# vr61-revB.net
KiCad netlist of a schematic drawn in EAGLE
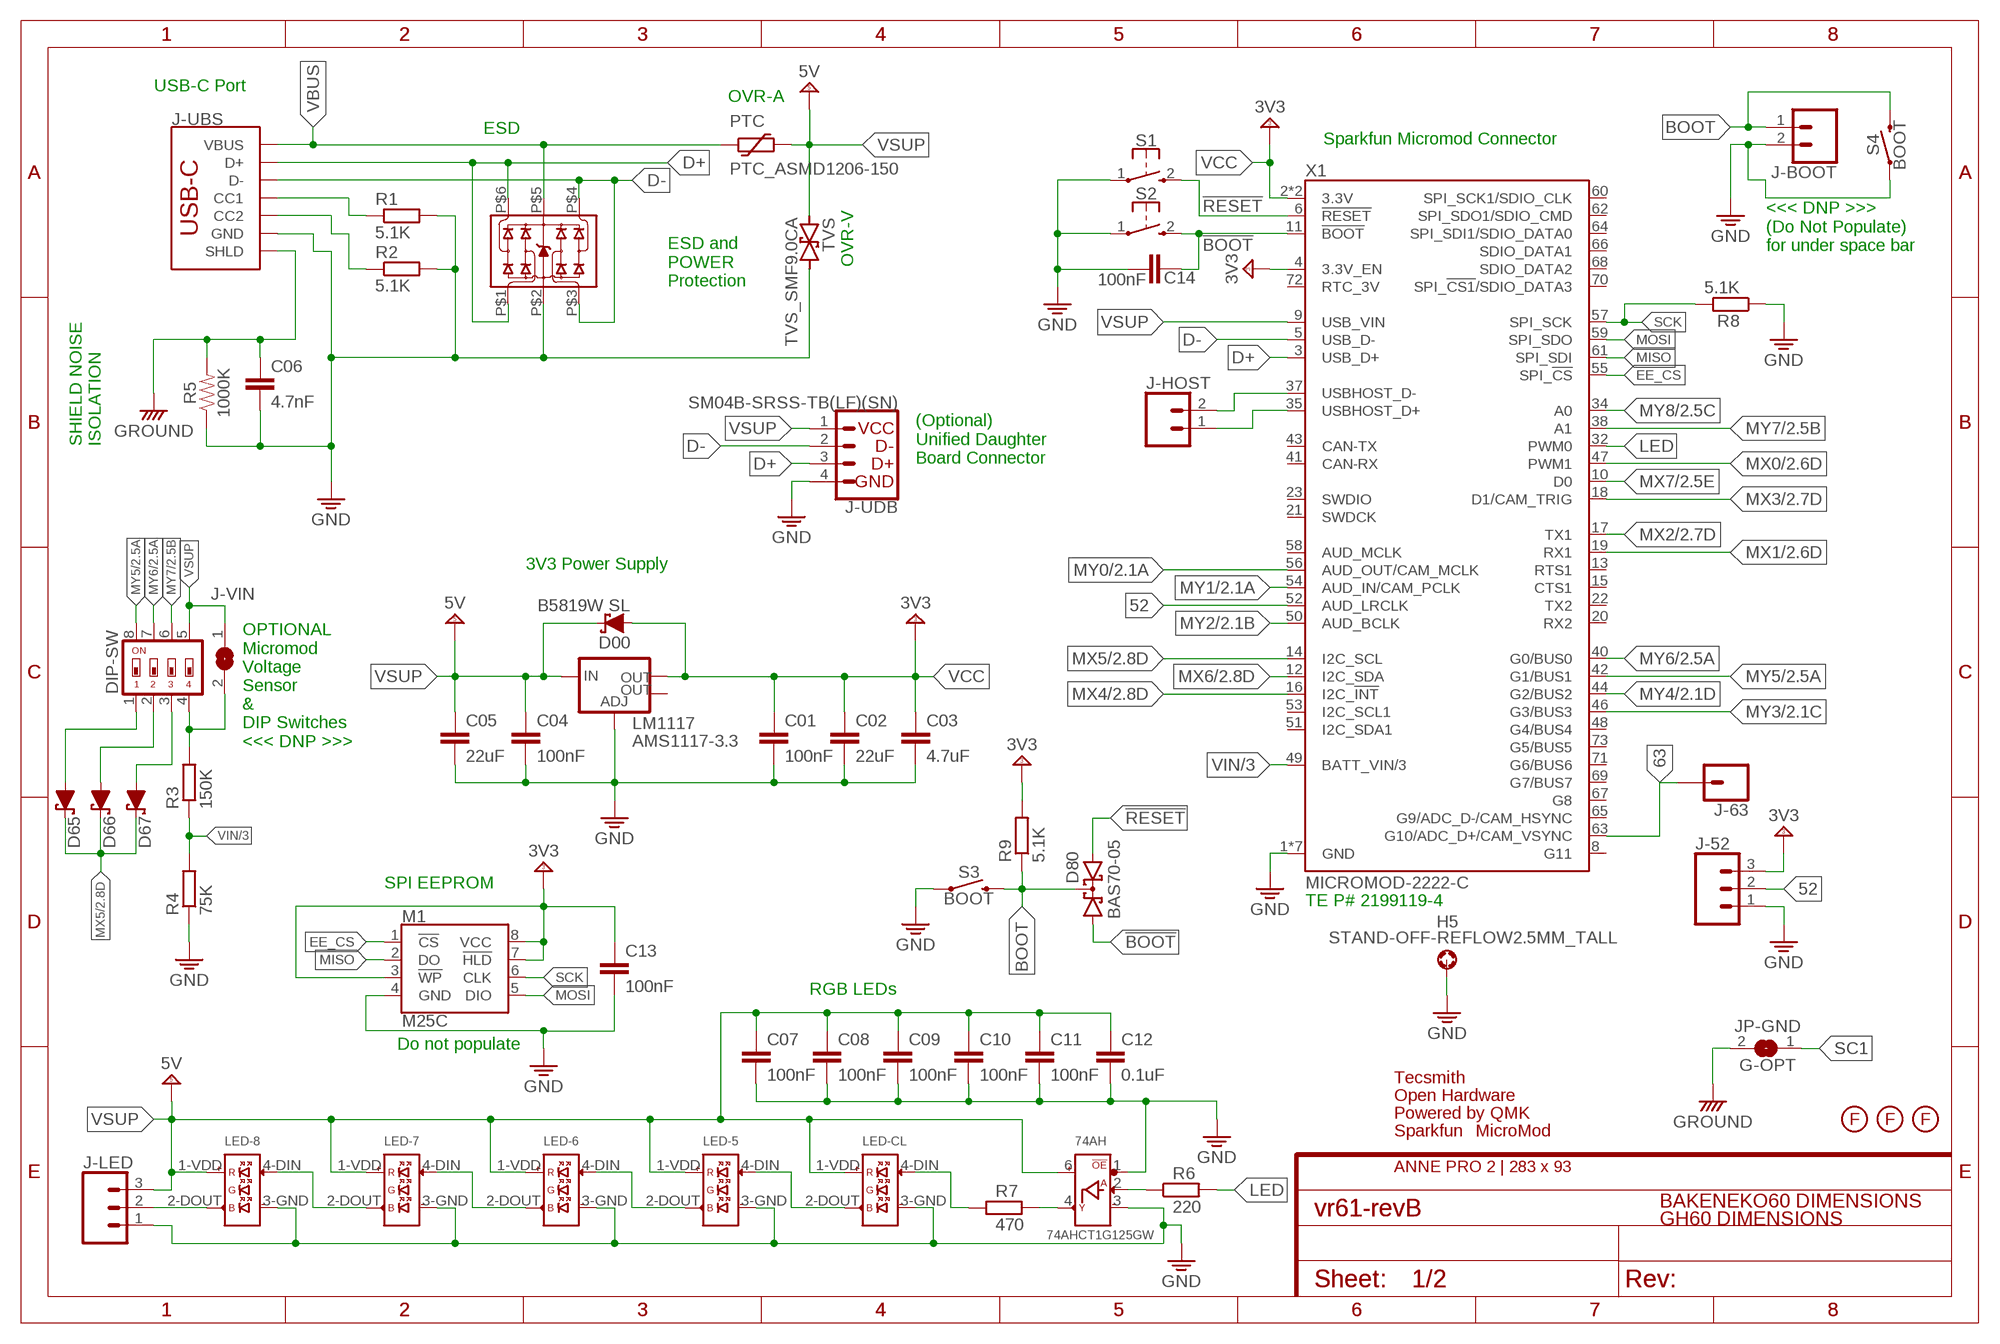
[diagram p0: schematic, sheet 1]
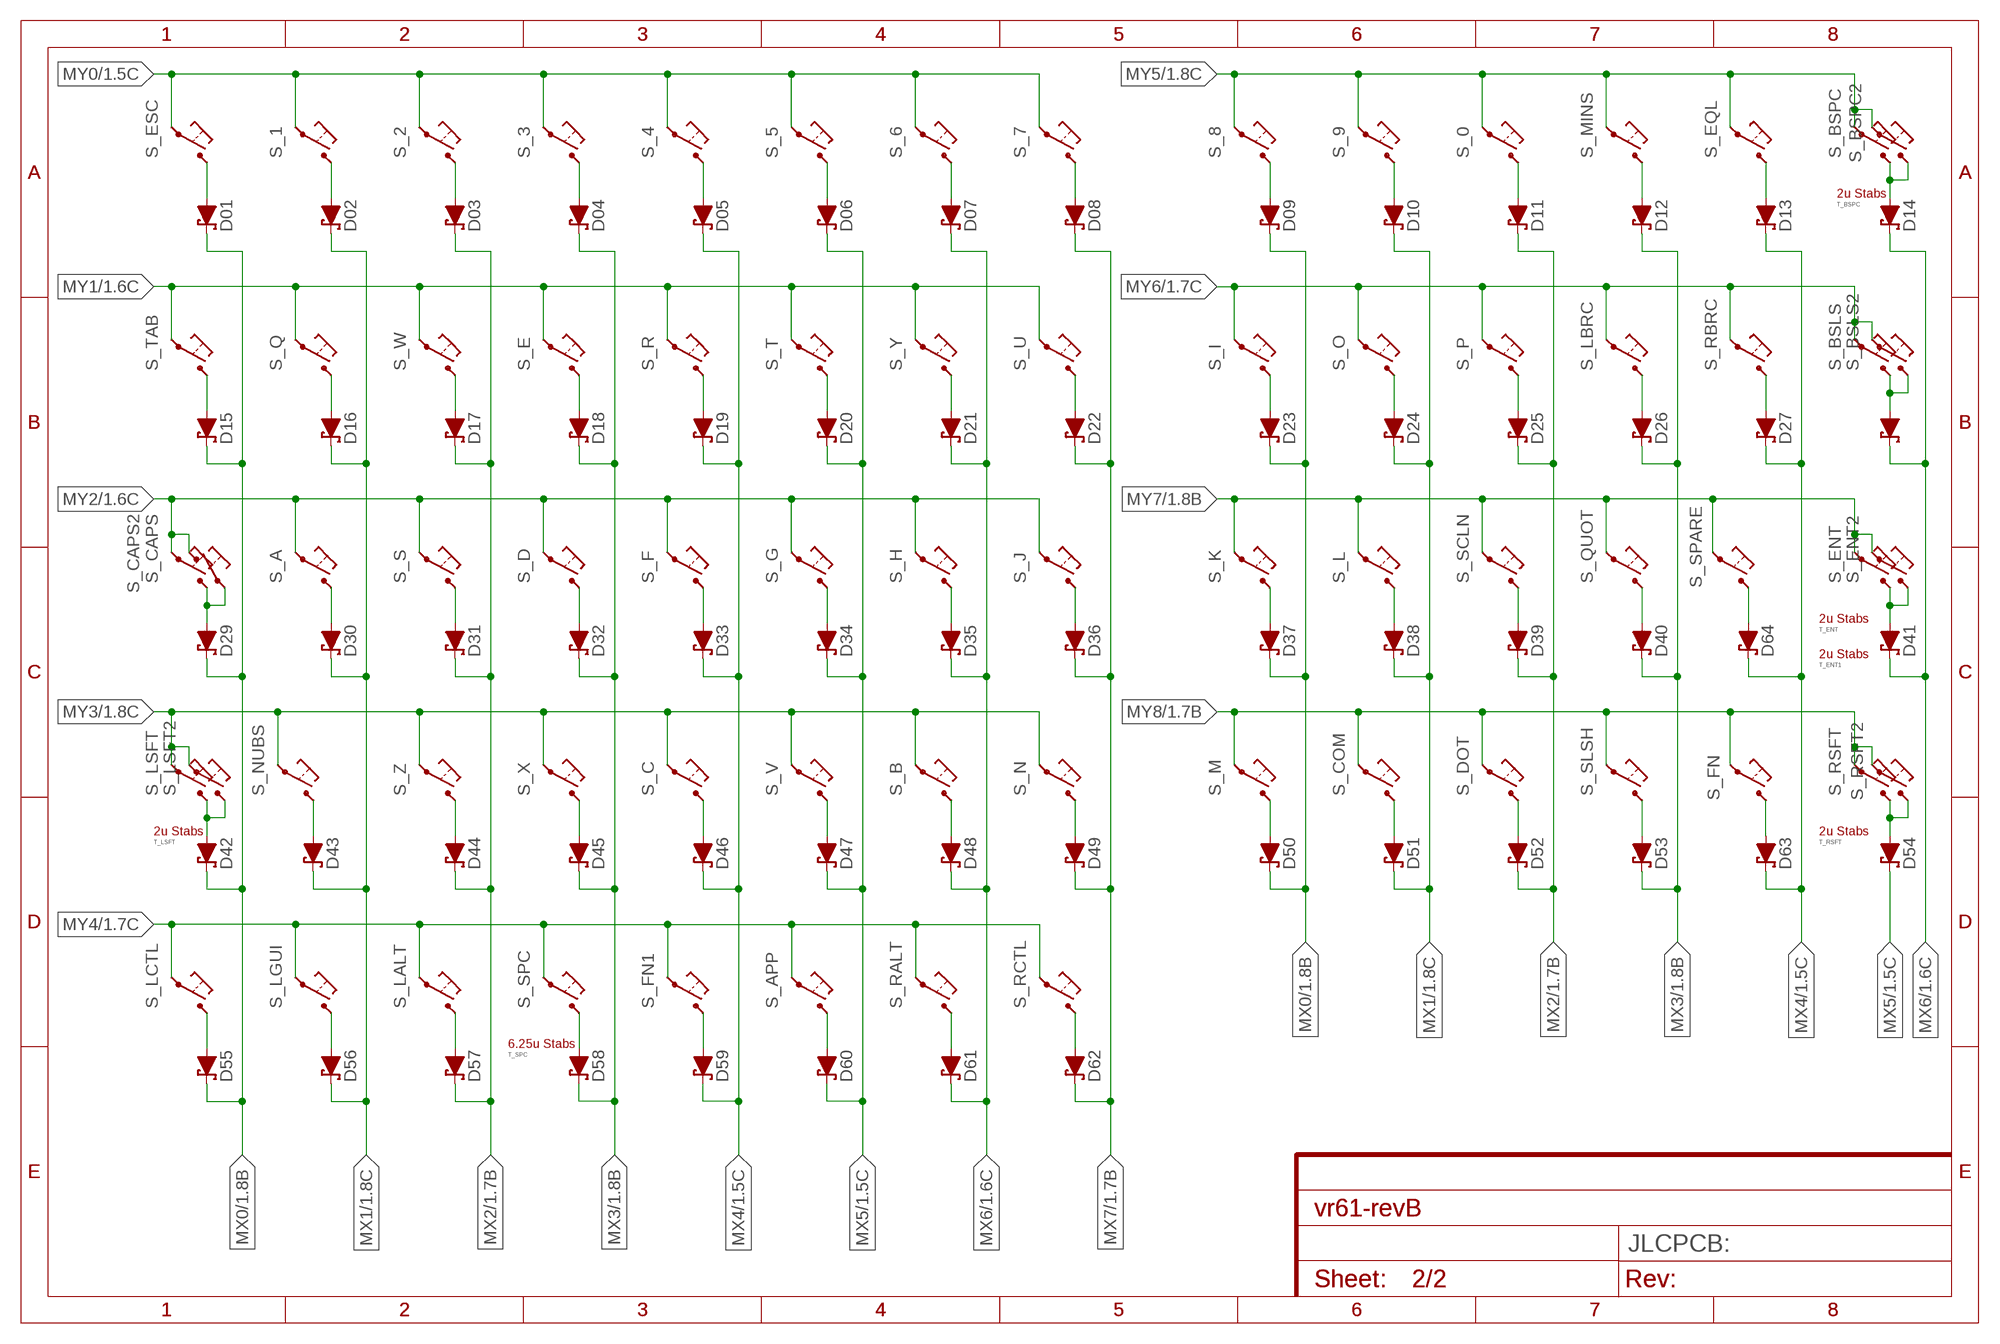
[diagram p1: schematic, sheet 2]

(export (version "E")
  (design (tool "Eeschema 10.0.6"))
  (components
    (comp (ref "D01")
      (value "1N5819WS")
      (footprint "eagle-import:SOD-123")
      (libsource (lib "eagle-import") (part "1N5819WS"))
    )
    (comp (ref "D02")
      (value "1N5819WS")
      (footprint "eagle-import:SOD-123")
      (libsource (lib "eagle-import") (part "1N5819WS"))
    )
    (comp (ref "D03")
      (value "1N5819WS")
      (footprint "eagle-import:SOD-123")
      (libsource (lib "eagle-import") (part "1N5819WS"))
    )
    (comp (ref "D04")
      (value "1N5819WS")
      (footprint "eagle-import:SOD-123")
      (libsource (lib "eagle-import") (part "1N5819WS"))
    )
    (comp (ref "D05")
      (value "1N5819WS")
      (footprint "eagle-import:SOD-123")
      (libsource (lib "eagle-import") (part "1N5819WS"))
    )
    (comp (ref "D06")
      (value "1N5819WS")
      (footprint "eagle-import:SOD-123")
      (libsource (lib "eagle-import") (part "1N5819WS"))
    )
    (comp (ref "D07")
      (value "1N5819WS")
      (footprint "eagle-import:SOD-123")
      (libsource (lib "eagle-import") (part "1N5819WS"))
    )
    (comp (ref "D08")
      (value "1N5819WS")
      (footprint "eagle-import:SOD-123")
      (libsource (lib "eagle-import") (part "1N5819WS"))
    )
    (comp (ref "D09")
      (value "1N5819WS")
      (footprint "eagle-import:SOD-123")
      (libsource (lib "eagle-import") (part "1N5819WS"))
    )
    (comp (ref "D10")
      (value "1N5819WS")
      (footprint "eagle-import:SOD-123")
      (libsource (lib "eagle-import") (part "1N5819WS"))
    )
    (comp (ref "D11")
      (value "1N5819WS")
      (footprint "eagle-import:SOD-123")
      (libsource (lib "eagle-import") (part "1N5819WS"))
    )
    (comp (ref "D12")
      (value "1N5819WS")
      (footprint "eagle-import:SOD-123")
      (libsource (lib "eagle-import") (part "1N5819WS"))
    )
    (comp (ref "D13")
      (value "1N5819WS")
      (footprint "eagle-import:SOD-123")
      (libsource (lib "eagle-import") (part "1N5819WS"))
    )
    (comp (ref "D14")
      (value "1N5819WS")
      (footprint "eagle-import:SOD-123")
      (libsource (lib "eagle-import") (part "1N5819WS"))
    )
    (comp (ref "D15")
      (value "1N5819WS")
      (footprint "eagle-import:SOD-123")
      (libsource (lib "eagle-import") (part "1N5819WS"))
    )
    (comp (ref "D16")
      (value "1N5819WS")
      (footprint "eagle-import:SOD-123")
      (libsource (lib "eagle-import") (part "1N5819WS"))
    )
    (comp (ref "D17")
      (value "1N5819WS")
      (footprint "eagle-import:SOD-123")
      (libsource (lib "eagle-import") (part "1N5819WS"))
    )
    (comp (ref "D18")
      (value "1N5819WS")
      (footprint "eagle-import:SOD-123")
      (libsource (lib "eagle-import") (part "1N5819WS"))
    )
    (comp (ref "D19")
      (value "1N5819WS")
      (footprint "eagle-import:SOD-123")
      (libsource (lib "eagle-import") (part "1N5819WS"))
    )
    (comp (ref "D20")
      (value "1N5819WS")
      (footprint "eagle-import:SOD-123")
      (libsource (lib "eagle-import") (part "1N5819WS"))
    )
    (comp (ref "D21")
      (value "1N5819WS")
      (footprint "eagle-import:SOD-123")
      (libsource (lib "eagle-import") (part "1N5819WS"))
    )
    (comp (ref "D22")
      (value "1N5819WS")
      (footprint "eagle-import:SOD-123")
      (libsource (lib "eagle-import") (part "1N5819WS"))
    )
    (comp (ref "D23")
      (value "1N5819WS")
      (footprint "eagle-import:SOD-123")
      (libsource (lib "eagle-import") (part "1N5819WS"))
    )
    (comp (ref "D24")
      (value "1N5819WS")
      (footprint "eagle-import:SOD-123")
      (libsource (lib "eagle-import") (part "1N5819WS"))
    )
    (comp (ref "D25")
      (value "1N5819WS")
      (footprint "eagle-import:SOD-123")
      (libsource (lib "eagle-import") (part "1N5819WS"))
    )
    (comp (ref "D26")
      (value "1N5819WS")
      (footprint "eagle-import:SOD-123")
      (libsource (lib "eagle-import") (part "1N5819WS"))
    )
    (comp (ref "D27")
      (value "1N5819WS")
      (footprint "eagle-import:SOD-123")
      (libsource (lib "eagle-import") (part "1N5819WS"))
    )
    (comp (ref "D28")
      (value "1N5819WS")
      (footprint "eagle-import:SOD-123")
      (libsource (lib "eagle-import") (part "1N5819WS"))
    )
    (comp (ref "D29")
      (value "1N5819WS")
      (footprint "eagle-import:SOD-123")
      (libsource (lib "eagle-import") (part "1N5819WS"))
    )
    (comp (ref "D30")
      (value "1N5819WS")
      (footprint "eagle-import:SOD-123")
      (libsource (lib "eagle-import") (part "1N5819WS"))
    )
    (comp (ref "D31")
      (value "1N5819WS")
      (footprint "eagle-import:SOD-123")
      (libsource (lib "eagle-import") (part "1N5819WS"))
    )
    (comp (ref "D32")
      (value "1N5819WS")
      (footprint "eagle-import:SOD-123")
      (libsource (lib "eagle-import") (part "1N5819WS"))
    )
    (comp (ref "D33")
      (value "1N5819WS")
      (footprint "eagle-import:SOD-123")
      (libsource (lib "eagle-import") (part "1N5819WS"))
    )
    (comp (ref "D34")
      (value "1N5819WS")
      (footprint "eagle-import:SOD-123")
      (libsource (lib "eagle-import") (part "1N5819WS"))
    )
    (comp (ref "D35")
      (value "1N5819WS")
      (footprint "eagle-import:SOD-123")
      (libsource (lib "eagle-import") (part "1N5819WS"))
    )
    (comp (ref "D36")
      (value "1N5819WS")
      (footprint "eagle-import:SOD-123")
      (libsource (lib "eagle-import") (part "1N5819WS"))
    )
    (comp (ref "D37")
      (value "1N5819WS")
      (footprint "eagle-import:SOD-123")
      (libsource (lib "eagle-import") (part "1N5819WS"))
    )
    (comp (ref "D38")
      (value "1N5819WS")
      (footprint "eagle-import:SOD-123")
      (libsource (lib "eagle-import") (part "1N5819WS"))
    )
    (comp (ref "D39")
      (value "1N5819WS")
      (footprint "eagle-import:SOD-123")
      (libsource (lib "eagle-import") (part "1N5819WS"))
    )
    (comp (ref "D40")
      (value "1N5819WS")
      (footprint "eagle-import:SOD-123")
      (libsource (lib "eagle-import") (part "1N5819WS"))
    )
    (comp (ref "D41")
      (value "1N5819WS")
      (footprint "eagle-import:SOD-123")
      (libsource (lib "eagle-import") (part "1N5819WS"))
    )
    (comp (ref "D42")
      (value "1N5819WS")
      (footprint "eagle-import:SOD-123")
      (libsource (lib "eagle-import") (part "1N5819WS"))
    )
    (comp (ref "D43")
      (value "1N5819WS")
      (footprint "eagle-import:SOD-123")
      (libsource (lib "eagle-import") (part "1N5819WS"))
    )
    (comp (ref "D44")
      (value "1N5819WS")
      (footprint "eagle-import:SOD-123")
      (libsource (lib "eagle-import") (part "1N5819WS"))
    )
    (comp (ref "D45")
      (value "1N5819WS")
      (footprint "eagle-import:SOD-123")
      (libsource (lib "eagle-import") (part "1N5819WS"))
    )
    (comp (ref "D46")
      (value "1N5819WS")
      (footprint "eagle-import:SOD-123")
      (libsource (lib "eagle-import") (part "1N5819WS"))
    )
    (comp (ref "D47")
      (value "1N5819WS")
      (footprint "eagle-import:SOD-123")
      (libsource (lib "eagle-import") (part "1N5819WS"))
    )
    (comp (ref "D48")
      (value "1N5819WS")
      (footprint "eagle-import:SOD-123")
      (libsource (lib "eagle-import") (part "1N5819WS"))
    )
    (comp (ref "D49")
      (value "1N5819WS")
      (footprint "eagle-import:SOD-123")
      (libsource (lib "eagle-import") (part "1N5819WS"))
    )
    (comp (ref "D50")
      (value "1N5819WS")
      (footprint "eagle-import:SOD-123")
      (libsource (lib "eagle-import") (part "1N5819WS"))
    )
    (comp (ref "D51")
      (value "1N5819WS")
      (footprint "eagle-import:SOD-123")
      (libsource (lib "eagle-import") (part "1N5819WS"))
    )
    (comp (ref "D52")
      (value "1N5819WS")
      (footprint "eagle-import:SOD-123")
      (libsource (lib "eagle-import") (part "1N5819WS"))
    )
    (comp (ref "D53")
      (value "1N5819WS")
      (footprint "eagle-import:SOD-123")
      (libsource (lib "eagle-import") (part "1N5819WS"))
    )
    (comp (ref "D54")
      (value "1N5819WS")
      (footprint "eagle-import:SOD-123")
      (libsource (lib "eagle-import") (part "1N5819WS"))
    )
    (comp (ref "D55")
      (value "1N5819WS")
      (footprint "eagle-import:SOD-123")
      (libsource (lib "eagle-import") (part "1N5819WS"))
    )
    (comp (ref "D56")
      (value "1N5819WS")
      (footprint "eagle-import:SOD-123")
      (libsource (lib "eagle-import") (part "1N5819WS"))
    )
    (comp (ref "D57")
      (value "1N5819WS")
      (footprint "eagle-import:SOD-123")
      (libsource (lib "eagle-import") (part "1N5819WS"))
    )
    (comp (ref "D58")
      (value "1N5819WS")
      (footprint "eagle-import:SOD-123")
      (libsource (lib "eagle-import") (part "1N5819WS"))
    )
    (comp (ref "D59")
      (value "1N5819WS")
      (footprint "eagle-import:SOD-123")
      (libsource (lib "eagle-import") (part "1N5819WS"))
    )
    (comp (ref "D60")
      (value "1N5819WS")
      (footprint "eagle-import:SOD-123")
      (libsource (lib "eagle-import") (part "1N5819WS"))
    )
    (comp (ref "D61")
      (value "1N5819WS")
      (footprint "eagle-import:SOD-123")
      (libsource (lib "eagle-import") (part "1N5819WS"))
    )
    (comp (ref "D62")
      (value "1N5819WS")
      (footprint "eagle-import:SOD-123")
      (libsource (lib "eagle-import") (part "1N5819WS"))
    )
    (comp (ref "D63")
      (value "1N5819WS")
      (footprint "eagle-import:SOD-123")
      (libsource (lib "eagle-import") (part "1N5819WS"))
    )
    (comp (ref "D64")
      (value "1N5819WS")
      (footprint "eagle-import:SOD-123")
      (libsource (lib "eagle-import") (part "1N5819WS"))
    )
    (comp (ref "S_0")
      (value "MX-5-PIN-HOTSWAP-PAD")
      (footprint "eagle-import:MX-5-PIN-HOTSWAP-PAD")
      (libsource (lib "eagle-import") (part "MX-5-PIN-HOTSWAP-PAD"))
    )
    (comp (ref "S_1")
      (value "MX-5-PIN-HOTSWAP-PAD")
      (footprint "eagle-import:MX-5-PIN-HOTSWAP-PAD")
      (libsource (lib "eagle-import") (part "MX-5-PIN-HOTSWAP-PAD"))
    )
    (comp (ref "S_2")
      (value "MX-5-PIN-HOTSWAP-PAD")
      (footprint "eagle-import:MX-5-PIN-HOTSWAP-PAD")
      (libsource (lib "eagle-import") (part "MX-5-PIN-HOTSWAP-PAD"))
    )
    (comp (ref "S_3")
      (value "MX-5-PIN-HOTSWAP-PAD")
      (footprint "eagle-import:MX-5-PIN-HOTSWAP-PAD")
      (libsource (lib "eagle-import") (part "MX-5-PIN-HOTSWAP-PAD"))
    )
    (comp (ref "S_4")
      (value "MX-5-PIN-HOTSWAP-PAD")
      (footprint "eagle-import:MX-5-PIN-HOTSWAP-PAD")
      (libsource (lib "eagle-import") (part "MX-5-PIN-HOTSWAP-PAD"))
    )
    (comp (ref "S_5")
      (value "MX-5-PIN-HOTSWAP-PAD")
      (footprint "eagle-import:MX-5-PIN-HOTSWAP-PAD")
      (libsource (lib "eagle-import") (part "MX-5-PIN-HOTSWAP-PAD"))
    )
    (comp (ref "S_6")
      (value "MX-5-PIN-HOTSWAP-PAD")
      (footprint "eagle-import:MX-5-PIN-HOTSWAP-PAD")
      (libsource (lib "eagle-import") (part "MX-5-PIN-HOTSWAP-PAD"))
    )
    (comp (ref "S_7")
      (value "MX-5-PIN-HOTSWAP-PAD")
      (footprint "eagle-import:MX-5-PIN-HOTSWAP-PAD")
      (libsource (lib "eagle-import") (part "MX-5-PIN-HOTSWAP-PAD"))
    )
    (comp (ref "S_8")
      (value "MX-5-PIN-HOTSWAP-PAD")
      (footprint "eagle-import:MX-5-PIN-HOTSWAP-PAD")
      (libsource (lib "eagle-import") (part "MX-5-PIN-HOTSWAP-PAD"))
    )
    (comp (ref "S_9")
      (value "MX-5-PIN-HOTSWAP-PAD")
      (footprint "eagle-import:MX-5-PIN-HOTSWAP-PAD")
      (libsource (lib "eagle-import") (part "MX-5-PIN-HOTSWAP-PAD"))
    )
    (comp (ref "S_A")
      (value "MX-5-PIN-HOTSWAP-PAD")
      (footprint "eagle-import:MX-5-PIN-HOTSWAP-PAD")
      (libsource (lib "eagle-import") (part "MX-5-PIN-HOTSWAP-PAD"))
    )
    (comp (ref "S_APP")
      (value "MX-5-PIN-HOTSWAP-PAD")
      (footprint "eagle-import:MX-5-PIN-HOTSWAP-PAD")
      (libsource (lib "eagle-import") (part "MX-5-PIN-HOTSWAP-PAD"))
    )
    (comp (ref "S_B")
      (value "MX-5-PIN-HOTSWAP-PAD")
      (footprint "eagle-import:MX-5-PIN-HOTSWAP-PAD")
      (libsource (lib "eagle-import") (part "MX-5-PIN-HOTSWAP-PAD"))
    )
    (comp (ref "S_BSLS")
      (value "MX-5-PIN-HOTSWAP-PAD")
      (footprint "eagle-import:MX-5-PIN-HOTSWAP-PAD")
      (libsource (lib "eagle-import") (part "MX-5-PIN-HOTSWAP-PAD"))
    )
    (comp (ref "S_BSLS2")
      (value "MX-5-PIN-HOTSWAP-PADNO-SILK")
      (footprint "eagle-import:MX-5-PIN-HOTSWAP-PAD-NS")
      (libsource (lib "eagle-import") (part "MX-5-PIN-HOTSWAP-PADNO-SILK"))
    )
    (comp (ref "S_BSPC")
      (value "MX-5-PIN-HOTSWAP-PAD")
      (footprint "eagle-import:MX-5-PIN-HOTSWAP-PAD")
      (libsource (lib "eagle-import") (part "MX-5-PIN-HOTSWAP-PAD"))
    )
    (comp (ref "S_BSPC2")
      (value "MX-5-PIN-MILMAX-3305-XNO-SILK")
      (footprint "eagle-import:MX-5-PIN-MILMAX-3305-X-NS")
      (libsource (lib "eagle-import") (part "MX-5-PIN-MILMAX-3305-XNO-SILK"))
    )
    (comp (ref "S_C")
      (value "MX-5-PIN-HOTSWAP-PAD")
      (footprint "eagle-import:MX-5-PIN-HOTSWAP-PAD")
      (libsource (lib "eagle-import") (part "MX-5-PIN-HOTSWAP-PAD"))
    )
    (comp (ref "S_CAPS")
      (value "MX-5-PIN-HOTSWAP-PAD")
      (footprint "eagle-import:MX-5-PIN-HOTSWAP-PAD")
      (libsource (lib "eagle-import") (part "MX-5-PIN-HOTSWAP-PAD"))
    )
    (comp (ref "S_CAPS2")
      (value "MX-5-PIN-MILMAX-3305-XNO-SILK")
      (footprint "eagle-import:MX-5-PIN-MILMAX-3305-X-NS")
      (libsource (lib "eagle-import") (part "MX-5-PIN-MILMAX-3305-XNO-SILK"))
    )
    (comp (ref "S_COM")
      (value "MX-5-PIN-HOTSWAP-PAD")
      (footprint "eagle-import:MX-5-PIN-HOTSWAP-PAD")
      (libsource (lib "eagle-import") (part "MX-5-PIN-HOTSWAP-PAD"))
    )
    (comp (ref "S_D")
      (value "MX-5-PIN-HOTSWAP-PAD")
      (footprint "eagle-import:MX-5-PIN-HOTSWAP-PAD")
      (libsource (lib "eagle-import") (part "MX-5-PIN-HOTSWAP-PAD"))
    )
    (comp (ref "S_DOT")
      (value "MX-5-PIN-HOTSWAP-PAD")
      (footprint "eagle-import:MX-5-PIN-HOTSWAP-PAD")
      (libsource (lib "eagle-import") (part "MX-5-PIN-HOTSWAP-PAD"))
    )
    (comp (ref "S_E")
      (value "MX-5-PIN-HOTSWAP-PAD")
      (footprint "eagle-import:MX-5-PIN-HOTSWAP-PAD")
      (libsource (lib "eagle-import") (part "MX-5-PIN-HOTSWAP-PAD"))
    )
    (comp (ref "S_ENT")
      (value "MX-5-PIN-HOTSWAP-PAD")
      (footprint "eagle-import:MX-5-PIN-HOTSWAP-PAD")
      (libsource (lib "eagle-import") (part "MX-5-PIN-HOTSWAP-PAD"))
    )
    (comp (ref "S_ENT2")
      (value "MX-5-PIN-HOTSWAP-PADNO-SILK")
      (footprint "eagle-import:MX-5-PIN-HOTSWAP-PAD-NS")
      (libsource (lib "eagle-import") (part "MX-5-PIN-HOTSWAP-PADNO-SILK"))
    )
    (comp (ref "S_EQL")
      (value "MX-5-PIN-HOTSWAP-PAD")
      (footprint "eagle-import:MX-5-PIN-HOTSWAP-PAD")
      (libsource (lib "eagle-import") (part "MX-5-PIN-HOTSWAP-PAD"))
    )
    (comp (ref "S_ESC")
      (value "MX-5-PIN-HOTSWAP-PAD")
      (footprint "eagle-import:MX-5-PIN-HOTSWAP-PAD")
      (libsource (lib "eagle-import") (part "MX-5-PIN-HOTSWAP-PAD"))
    )
    (comp (ref "S_F")
      (value "MX-5-PIN-HOTSWAP-PAD")
      (footprint "eagle-import:MX-5-PIN-HOTSWAP-PAD")
      (libsource (lib "eagle-import") (part "MX-5-PIN-HOTSWAP-PAD"))
    )
    (comp (ref "S_FN")
      (value "MX-5-PIN-MILMAX-3305-XNO-SILK")
      (footprint "eagle-import:MX-5-PIN-MILMAX-3305-X-NS")
      (libsource (lib "eagle-import") (part "MX-5-PIN-MILMAX-3305-XNO-SILK"))
    )
    (comp (ref "S_FN1")
      (value "MX-5-PIN-HOTSWAP-PAD")
      (footprint "eagle-import:MX-5-PIN-HOTSWAP-PAD")
      (libsource (lib "eagle-import") (part "MX-5-PIN-HOTSWAP-PAD"))
    )
    (comp (ref "S_G")
      (value "MX-5-PIN-HOTSWAP-PAD")
      (footprint "eagle-import:MX-5-PIN-HOTSWAP-PAD")
      (libsource (lib "eagle-import") (part "MX-5-PIN-HOTSWAP-PAD"))
    )
    (comp (ref "S_H")
      (value "MX-5-PIN-HOTSWAP-PAD")
      (footprint "eagle-import:MX-5-PIN-HOTSWAP-PAD")
      (libsource (lib "eagle-import") (part "MX-5-PIN-HOTSWAP-PAD"))
    )
    (comp (ref "S_I")
      (value "MX-5-PIN-HOTSWAP-PAD")
      (footprint "eagle-import:MX-5-PIN-HOTSWAP-PAD")
      (libsource (lib "eagle-import") (part "MX-5-PIN-HOTSWAP-PAD"))
    )
    (comp (ref "S_J")
      (value "MX-5-PIN-HOTSWAP-PAD")
      (footprint "eagle-import:MX-5-PIN-HOTSWAP-PAD")
      (libsource (lib "eagle-import") (part "MX-5-PIN-HOTSWAP-PAD"))
    )
    (comp (ref "S_K")
      (value "MX-5-PIN-HOTSWAP-PAD")
      (footprint "eagle-import:MX-5-PIN-HOTSWAP-PAD")
      (libsource (lib "eagle-import") (part "MX-5-PIN-HOTSWAP-PAD"))
    )
    (comp (ref "S_L")
      (value "MX-5-PIN-HOTSWAP-PAD")
      (footprint "eagle-import:MX-5-PIN-HOTSWAP-PAD")
      (libsource (lib "eagle-import") (part "MX-5-PIN-HOTSWAP-PAD"))
    )
    (comp (ref "S_LALT")
      (value "MX-5-PIN-HOTSWAP-PAD")
      (footprint "eagle-import:MX-5-PIN-HOTSWAP-PAD")
      (libsource (lib "eagle-import") (part "MX-5-PIN-HOTSWAP-PAD"))
    )
    (comp (ref "S_LBRC")
      (value "MX-5-PIN-HOTSWAP-PAD")
      (footprint "eagle-import:MX-5-PIN-HOTSWAP-PAD")
      (libsource (lib "eagle-import") (part "MX-5-PIN-HOTSWAP-PAD"))
    )
    (comp (ref "S_LCTL")
      (value "MX-5-PIN-HOTSWAP-PAD")
      (footprint "eagle-import:MX-5-PIN-HOTSWAP-PAD")
      (libsource (lib "eagle-import") (part "MX-5-PIN-HOTSWAP-PAD"))
    )
    (comp (ref "S_LGUI")
      (value "MX-5-PIN-HOTSWAP-PAD")
      (footprint "eagle-import:MX-5-PIN-HOTSWAP-PAD")
      (libsource (lib "eagle-import") (part "MX-5-PIN-HOTSWAP-PAD"))
    )
    (comp (ref "S_LSFT")
      (value "MX-5-PIN-HOTSWAP-PAD")
      (footprint "eagle-import:MX-5-PIN-HOTSWAP-PAD")
      (libsource (lib "eagle-import") (part "MX-5-PIN-HOTSWAP-PAD"))
    )
    (comp (ref "S_LSFT2")
      (value "MX-5-PIN-HOTSWAP-PADNO-SILK")
      (footprint "eagle-import:MX-5-PIN-HOTSWAP-PAD-NS")
      (libsource (lib "eagle-import") (part "MX-5-PIN-HOTSWAP-PADNO-SILK"))
    )
    (comp (ref "S_M")
      (value "MX-5-PIN-HOTSWAP-PAD")
      (footprint "eagle-import:MX-5-PIN-HOTSWAP-PAD")
      (libsource (lib "eagle-import") (part "MX-5-PIN-HOTSWAP-PAD"))
    )
    (comp (ref "S_MINS")
      (value "MX-5-PIN-HOTSWAP-PAD")
      (footprint "eagle-import:MX-5-PIN-HOTSWAP-PAD")
      (libsource (lib "eagle-import") (part "MX-5-PIN-HOTSWAP-PAD"))
    )
    (comp (ref "S_N")
      (value "MX-5-PIN-HOTSWAP-PAD")
      (footprint "eagle-import:MX-5-PIN-HOTSWAP-PAD")
      (libsource (lib "eagle-import") (part "MX-5-PIN-HOTSWAP-PAD"))
    )
    (comp (ref "S_NUBS")
      (value "MX-5-PIN-HOTSWAP-PADNO-SILK")
      (footprint "eagle-import:MX-5-PIN-HOTSWAP-PAD-NS")
      (libsource (lib "eagle-import") (part "MX-5-PIN-HOTSWAP-PADNO-SILK"))
    )
    (comp (ref "S_O")
      (value "MX-5-PIN-HOTSWAP-PAD")
      (footprint "eagle-import:MX-5-PIN-HOTSWAP-PAD")
      (libsource (lib "eagle-import") (part "MX-5-PIN-HOTSWAP-PAD"))
    )
    (comp (ref "S_P")
      (value "MX-5-PIN-HOTSWAP-PAD")
      (footprint "eagle-import:MX-5-PIN-HOTSWAP-PAD")
      (libsource (lib "eagle-import") (part "MX-5-PIN-HOTSWAP-PAD"))
    )
    (comp (ref "S_Q")
      (value "MX-5-PIN-HOTSWAP-PAD")
      (footprint "eagle-import:MX-5-PIN-HOTSWAP-PAD")
      (libsource (lib "eagle-import") (part "MX-5-PIN-HOTSWAP-PAD"))
    )
    (comp (ref "S_QUOT")
      (value "MX-5-PIN-HOTSWAP-PAD")
      (footprint "eagle-import:MX-5-PIN-HOTSWAP-PAD")
      (libsource (lib "eagle-import") (part "MX-5-PIN-HOTSWAP-PAD"))
    )
    (comp (ref "S_R")
      (value "MX-5-PIN-HOTSWAP-PAD")
      (footprint "eagle-import:MX-5-PIN-HOTSWAP-PAD")
      (libsource (lib "eagle-import") (part "MX-5-PIN-HOTSWAP-PAD"))
    )
    (comp (ref "S_RALT")
      (value "MX-5-PIN-HOTSWAP-PAD")
      (footprint "eagle-import:MX-5-PIN-HOTSWAP-PAD")
      (libsource (lib "eagle-import") (part "MX-5-PIN-HOTSWAP-PAD"))
    )
    (comp (ref "S_RBRC")
      (value "MX-5-PIN-HOTSWAP-PAD")
      (footprint "eagle-import:MX-5-PIN-HOTSWAP-PAD")
      (libsource (lib "eagle-import") (part "MX-5-PIN-HOTSWAP-PAD"))
    )
    (comp (ref "S_RCTL")
      (value "MX-5-PIN-HOTSWAP-PAD")
      (footprint "eagle-import:MX-5-PIN-HOTSWAP-PAD")
      (libsource (lib "eagle-import") (part "MX-5-PIN-HOTSWAP-PAD"))
    )
    (comp (ref "S_RSFT")
      (value "MX-5-PIN-HOTSWAP-PAD")
      (footprint "eagle-import:MX-5-PIN-HOTSWAP-PAD")
      (libsource (lib "eagle-import") (part "MX-5-PIN-HOTSWAP-PAD"))
    )
    (comp (ref "S_RSFT2")
      (value "MX-5-PIN-MILMAX-3305-XNO-SILK")
      (footprint "eagle-import:MX-5-PIN-MILMAX-3305-X-NS")
      (libsource (lib "eagle-import") (part "MX-5-PIN-MILMAX-3305-XNO-SILK"))
    )
    (comp (ref "S_S")
      (value "MX-5-PIN-HOTSWAP-PAD")
      (footprint "eagle-import:MX-5-PIN-HOTSWAP-PAD")
      (libsource (lib "eagle-import") (part "MX-5-PIN-HOTSWAP-PAD"))
    )
    (comp (ref "S_SCLN")
      (value "MX-5-PIN-HOTSWAP-PAD")
      (footprint "eagle-import:MX-5-PIN-HOTSWAP-PAD")
      (libsource (lib "eagle-import") (part "MX-5-PIN-HOTSWAP-PAD"))
    )
    (comp (ref "S_SLSH")
      (value "MX-5-PIN-HOTSWAP-PAD")
      (footprint "eagle-import:MX-5-PIN-HOTSWAP-PAD")
      (libsource (lib "eagle-import") (part "MX-5-PIN-HOTSWAP-PAD"))
    )
    (comp (ref "S_SPARE")
      (value "MX-5-PIN-MILMAX-3305-XNO-SILK")
      (footprint "eagle-import:MX-5-PIN-MILMAX-3305-X-NS")
      (libsource (lib "eagle-import") (part "MX-5-PIN-MILMAX-3305-XNO-SILK"))
    )
    (comp (ref "S_SPC")
      (value "MX-5-PIN-HOTSWAP-PAD")
      (footprint "eagle-import:MX-5-PIN-HOTSWAP-PAD")
      (libsource (lib "eagle-import") (part "MX-5-PIN-HOTSWAP-PAD"))
    )
    (comp (ref "S_T")
      (value "MX-5-PIN-HOTSWAP-PAD")
      (footprint "eagle-import:MX-5-PIN-HOTSWAP-PAD")
      (libsource (lib "eagle-import") (part "MX-5-PIN-HOTSWAP-PAD"))
    )
    (comp (ref "S_TAB")
      (value "MX-5-PIN-HOTSWAP-PAD")
      (footprint "eagle-import:MX-5-PIN-HOTSWAP-PAD")
      (libsource (lib "eagle-import") (part "MX-5-PIN-HOTSWAP-PAD"))
    )
    (comp (ref "S_U")
      (value "MX-5-PIN-HOTSWAP-PAD")
      (footprint "eagle-import:MX-5-PIN-HOTSWAP-PAD")
      (libsource (lib "eagle-import") (part "MX-5-PIN-HOTSWAP-PAD"))
    )
    (comp (ref "S_V")
      (value "MX-5-PIN-HOTSWAP-PAD")
      (footprint "eagle-import:MX-5-PIN-HOTSWAP-PAD")
      (libsource (lib "eagle-import") (part "MX-5-PIN-HOTSWAP-PAD"))
    )
    (comp (ref "S_W")
      (value "MX-5-PIN-HOTSWAP-PAD")
      (footprint "eagle-import:MX-5-PIN-HOTSWAP-PAD")
      (libsource (lib "eagle-import") (part "MX-5-PIN-HOTSWAP-PAD"))
    )
    (comp (ref "S_X")
      (value "MX-5-PIN-HOTSWAP-PAD")
      (footprint "eagle-import:MX-5-PIN-HOTSWAP-PAD")
      (libsource (lib "eagle-import") (part "MX-5-PIN-HOTSWAP-PAD"))
    )
    (comp (ref "S_Y")
      (value "MX-5-PIN-HOTSWAP-PAD")
      (footprint "eagle-import:MX-5-PIN-HOTSWAP-PAD")
      (libsource (lib "eagle-import") (part "MX-5-PIN-HOTSWAP-PAD"))
    )
    (comp (ref "S_Z")
      (value "MX-5-PIN-HOTSWAP-PAD")
      (footprint "eagle-import:MX-5-PIN-HOTSWAP-PAD")
      (libsource (lib "eagle-import") (part "MX-5-PIN-HOTSWAP-PAD"))
    )
    (comp (ref "T_BSPC")
      (value "MX-STABS-200U")
      (footprint "eagle-import:MX-STABS-200U")
      (libsource (lib "eagle-import") (part "MX-STABS-200U"))
    )
    (comp (ref "T_ENT")
      (value "MX-STABS-200U")
      (footprint "eagle-import:MX-STABS-200U")
      (libsource (lib "eagle-import") (part "MX-STABS-200U"))
    )
    (comp (ref "T_ENT1")
      (value "MX-STABS-200U")
      (footprint "eagle-import:MX-STABS-200U")
      (libsource (lib "eagle-import") (part "MX-STABS-200U"))
    )
    (comp (ref "T_LSFT")
      (value "MX-STABS-200U")
      (footprint "eagle-import:MX-STABS-200U")
      (libsource (lib "eagle-import") (part "MX-STABS-200U"))
    )
    (comp (ref "T_RSFT")
      (value "MX-STABS-200U")
      (footprint "eagle-import:MX-STABS-200U")
      (libsource (lib "eagle-import") (part "MX-STABS-200U"))
    )
    (comp (ref "T_SPC")
      (value "MX-STABS-625U")
      (footprint "eagle-import:MX-STABS-625U")
      (libsource (lib "eagle-import") (part "MX-STABS-625U"))
    )
    (comp (ref "U$26")
      (value "?")
      (footprint "eagle-import:JLC_ORDER_NUMBER_QR_5X5")
      (libsource (lib "eagle-import") (part "JLC_ORDER_NUMBER_QRQR_5X5"))
    )
    (comp (ref "74AH")
      (value "74AHCT1G125GW")
      (footprint "eagle-import:SC-88A__TSSOP5__SOT353-1")
      (libsource (lib "eagle-import") (part "74AHCT1G125GW"))
    )
    (comp (ref "C01")
      (value "100nF")
      (footprint "eagle-import:0603")
      (libsource (lib "eagle-import") (part "0.1UF-0603-25V-5%"))
    )
    (comp (ref "C02")
      (value "22uF")
      (footprint "eagle-import:0603")
      (libsource (lib "eagle-import") (part "0.22UF-0603-25V-10%"))
    )
    (comp (ref "C03")
      (value "4.7uF")
      (footprint "eagle-import:0603")
      (libsource (lib "eagle-import") (part "1.0NF/1000PF-0603-50V-10%"))
    )
    (comp (ref "C04")
      (value "100nF")
      (footprint "eagle-import:0603")
      (libsource (lib "eagle-import") (part "0.1UF-0603-25V-5%"))
    )
    (comp (ref "C05")
      (value "22uF")
      (footprint "eagle-import:0603")
      (libsource (lib "eagle-import") (part "0.22UF-0603-25V-10%"))
    )
    (comp (ref "C06")
      (value "4.7nF")
      (footprint "eagle-import:0603")
      (libsource (lib "eagle-import") (part "0.1UF-0603-25V-5%"))
    )
    (comp (ref "C07")
      (value "100nF")
      (footprint "eagle-import:C0603")
      (libsource (lib "eagle-import") (part "C-EUC0603"))
    )
    (comp (ref "C08")
      (value "100nF")
      (footprint "eagle-import:C0603")
      (libsource (lib "eagle-import") (part "C-EUC0603"))
    )
    (comp (ref "C09")
      (value "100nF")
      (footprint "eagle-import:C0603")
      (libsource (lib "eagle-import") (part "C-EUC0603"))
    )
    (comp (ref "C10")
      (value "100nF")
      (footprint "eagle-import:C0603")
      (libsource (lib "eagle-import") (part "C-EUC0603"))
    )
    (comp (ref "C11")
      (value "100nF")
      (footprint "eagle-import:C0603")
      (libsource (lib "eagle-import") (part "C-EUC0603"))
    )
    (comp (ref "C12")
      (value "0.1uF")
      (footprint "eagle-import:C0603")
      (libsource (lib "eagle-import") (part "C-EUC0603"))
    )
    (comp (ref "C13")
      (value "100nF")
      (footprint "eagle-import:C0603")
      (libsource (lib "eagle-import") (part "C-EUC0603"))
    )
    (comp (ref "C14")
      (value "100nF")
      (footprint "eagle-import:C0603")
      (libsource (lib "eagle-import") (part "C-EUC0603"))
    )
    (comp (ref "D00")
      (value "B5819W SL")
      (footprint "eagle-import:SOD-123")
      (libsource (lib "eagle-import") (part "1N5819WS"))
    )
    (comp (ref "D65")
      (value "1N5819WS")
      (footprint "eagle-import:SOD-123")
      (libsource (lib "eagle-import") (part "1N5819WS"))
    )
    (comp (ref "D66")
      (value "1N5819WS")
      (footprint "eagle-import:SOD-123")
      (libsource (lib "eagle-import") (part "1N5819WS"))
    )
    (comp (ref "D67")
      (value "1N5819WS")
      (footprint "eagle-import:SOD-123")
      (libsource (lib "eagle-import") (part "1N5819WS"))
    )
    (comp (ref "D80")
      (value "BAS70-05")
      (footprint "eagle-import:SOT23")
      (libsource (lib "eagle-import") (part "BAS70-05"))
    )
    (comp (ref "DIP-SW")
      (value "DIP004")
      (footprint "eagle-import:DIP-1.27-004")
      (libsource (lib "eagle-import") (part "DIP004"))
    )
    (comp (ref "ESD")
      (value "ESD_SRV05-4")
      (footprint "eagle-import:SOT-23-6L")
      (libsource (lib "eagle-import") (part "ESD_SRV05-4"))
    )
    (comp (ref "FP_AP2")
      (value "FOOTPRINT-AP2")
      (footprint "eagle-import:FOOTPRINT-AP2")
      (libsource (lib "eagle-import") (part "FOOTPRINT-AP2"))
    )
    (comp (ref "H5")
      (value "STAND-OFF-REFLOW2.5MM_TALL")
      (footprint "eagle-import:STAND-OFF-REFLOW-M2.5")
      (libsource (lib "eagle-import") (part "STAND-OFF-REFLOW2.5MM_TALL"))
    )
    (comp (ref "J-52")
      (value "CONN_03")
      (footprint "eagle-import:1X03")
      (libsource (lib "eagle-import") (part "CONN_03"))
    )
    (comp (ref "J-63")
      (value "CONN_01")
      (footprint "eagle-import:1X01")
      (libsource (lib "eagle-import") (part "CONN_01"))
    )
    (comp (ref "J-BOOT")
      (value "CONN_02")
      (footprint "eagle-import:1X02")
      (libsource (lib "eagle-import") (part "CONN_02"))
    )
    (comp (ref "J-HOST")
      (value "CONN_02")
      (footprint "eagle-import:1X02")
      (libsource (lib "eagle-import") (part "CONN_02"))
    )
    (comp (ref "J-LED")
      (value "CONN_03")
      (footprint "eagle-import:1X03")
      (libsource (lib "eagle-import") (part "CONN_03"))
    )
    (comp (ref "J-UBS")
      (value "USB_C_2-LAYER")
      (footprint "eagle-import:USB-C-16P")
      (libsource (lib "eagle-import") (part "USB_C_2-LAYER"))
    )
    (comp (ref "J-UDB")
      (value "SM04B-SRSS-TB(LF)(SN)")
      (footprint "eagle-import:1X04_1MM_RA")
      (libsource (lib "eagle-import") (part "C3_UNIFIEDJS-1MM"))
    )
    (comp (ref "J-VIN")
      (value "JUMPER-1X2")
      (footprint "eagle-import:SOLDERJUMPER_ARROW_NOPASTE")
      (libsource (lib "eagle-import") (part "JUMPER-1X2"))
    )
    (comp (ref "JP-GND")
      (value "G-OPT")
      (footprint "eagle-import:SOLDERJUMPER_ARROW_NOPASTE")
      (libsource (lib "eagle-import") (part "JUMPER-1X2"))
    )
    (comp (ref "LED-5")
      (value "SK6812-E-REVERSE")
      (footprint "eagle-import:SK6812-E-MILL")
      (libsource (lib "eagle-import") (part "SK6812-E-REVERSE"))
    )
    (comp (ref "LED-6")
      (value "SK6812-E-REVERSE")
      (footprint "eagle-import:SK6812-E-MILL")
      (libsource (lib "eagle-import") (part "SK6812-E-REVERSE"))
    )
    (comp (ref "LED-7")
      (value "SK6812-E-REVERSE")
      (footprint "eagle-import:SK6812-E-MILL")
      (libsource (lib "eagle-import") (part "SK6812-E-REVERSE"))
    )
    (comp (ref "LED-8")
      (value "SK6812-E-REVERSE")
      (footprint "eagle-import:SK6812-E-MILL")
      (libsource (lib "eagle-import") (part "SK6812-E-REVERSE"))
    )
    (comp (ref "LED-CL")
      (value "SK6812-E-REVERSE")
      (footprint "eagle-import:SK6812-E-MILL")
      (libsource (lib "eagle-import") (part "SK6812-E-REVERSE"))
    )
    (comp (ref "LM1117")
      (value "AMS1117-3.3")
      (footprint "eagle-import:SOT223")
      (libsource (lib "eagle-import") (part "V_REG_LM1117SOT223"))
    )
    (comp (ref "LOGO1")
      (value "OSHW-LOGOL")
      (footprint "eagle-import:OSHW-LOGO-L")
      (libsource (lib "eagle-import") (part "OSHW-LOGOL"))
    )
    (comp (ref "M1")
      (value "M25C")
      (footprint "eagle-import:8-SOIC")
      (libsource (lib "eagle-import") (part "M25C"))
    )
    (comp (ref "PTC")
      (value "PTC_ASMD1206-150")
      (footprint "eagle-import:SMD_PTC")
      (libsource (lib "eagle-import") (part "PTC_ASMD1206"))
    )
    (comp (ref "R1")
      (value "5.1K")
      (footprint "eagle-import:R0603")
      (libsource (lib "eagle-import") (part "R-EU_R0603"))
    )
    (comp (ref "R2")
      (value "5.1K")
      (footprint "eagle-import:R0603")
      (libsource (lib "eagle-import") (part "R-EU_R0603"))
    )
    (comp (ref "R3")
      (value "150K")
      (footprint "eagle-import:R0603")
      (libsource (lib "eagle-import") (part "R-EU_R0603"))
    )
    (comp (ref "R4")
      (value "75K")
      (footprint "eagle-import:R0603")
      (libsource (lib "eagle-import") (part "R-EU_R0603"))
    )
    (comp (ref "R5")
      (value "1000K")
      (footprint "eagle-import:0603")
      (libsource (lib "eagle-import") (part "75KOHM-0603-1/10W-1%"))
    )
    (comp (ref "R6")
      (value "220")
      (footprint "eagle-import:R0603")
      (libsource (lib "eagle-import") (part "R-EU_R0603"))
    )
    (comp (ref "R7")
      (value "470")
      (footprint "eagle-import:R0603")
      (libsource (lib "eagle-import") (part "R-EU_R0603"))
    )
    (comp (ref "R8")
      (value "5.1K")
      (footprint "eagle-import:R0603")
      (libsource (lib "eagle-import") (part "R-EU_R0603"))
    )
    (comp (ref "R9")
      (value "5.1K")
      (footprint "eagle-import:R0603")
      (libsource (lib "eagle-import") (part "R-EU_R0603"))
    )
    (comp (ref "S1")
      (value "MOMENTARY-SWITCH-SPST-1")
      (footprint "eagle-import:SKRKAEE020")
      (libsource (lib "eagle-import") (part "MOMENTARY-SWITCH-SPST-1"))
    )
    (comp (ref "S2")
      (value "MOMENTARY-SWITCH-SPST-1")
      (footprint "eagle-import:SKRKAEE020")
      (libsource (lib "eagle-import") (part "MOMENTARY-SWITCH-SPST-1"))
    )
    (comp (ref "S3")
      (value "BOOT")
      (footprint "eagle-import:TACTILE_SWITCH_SMD_5.2MM")
      (libsource (lib "eagle-import") (part "MOMENTARY-SWITCH-SPST-SMD-5.2-TALL-REDUNDANT"))
    )
    (comp (ref "S4")
      (value "BOOT")
      (footprint "eagle-import:TACTILE_SWITCH_SMD_5.2MM")
      (libsource (lib "eagle-import") (part "MOMENTARY-SWITCH-SPST-SMD-5.2-TALL-REDUNDANT"))
    )
    (comp (ref "TVS")
      (value "TVS_SMF9.0CA")
      (footprint "eagle-import:SOD123FL-BI")
      (libsource (lib "eagle-import") (part "TVS_SMF9.0CA"))
    )
    (comp (ref "U$3")
      (value "MICROMOD-LOGO")
      (footprint "eagle-import:MICROMOD-LOGO")
      (libsource (lib "eagle-import") (part "MICROMOD-LOGO"))
    )
    (comp (ref "U$5")
      (value "SPARKFUN_LOGO0.2")
      (footprint "eagle-import:SFE_LOGO_NAME_FLAME_.2")
      (libsource (lib "eagle-import") (part "SPARKFUN_LOGO0.2"))
    )
    (comp (ref "U$6")
      (value "QMK_LOGO")
      (footprint "eagle-import:QMK_LOGO")
      (libsource (lib "eagle-import") (part "QMK_LOGO"))
    )
    (comp (ref "U$8")
      (value "TECSMITH-LOGOLONG")
      (footprint "eagle-import:TECSMITH-NAME")
      (libsource (lib "eagle-import") (part "TECSMITH-LOGOLONG"))
    )
    (comp (ref "U$20")
      (value "FIDUCIAL")
      (footprint "eagle-import:FIDUCIAL")
      (libsource (lib "eagle-import") (part "FIDUCIAL"))
    )
    (comp (ref "U$21")
      (value "FIDUCIAL")
      (footprint "eagle-import:FIDUCIAL")
      (libsource (lib "eagle-import") (part "FIDUCIAL"))
    )
    (comp (ref "U$22")
      (value "FIDUCIAL")
      (footprint "eagle-import:FIDUCIAL")
      (libsource (lib "eagle-import") (part "FIDUCIAL"))
    )
    (comp (ref "U$24")
      (value "FOOTPRINT-BAKENEKO60")
      (footprint "eagle-import:FOOTPRINT-BAKENEKO60")
      (libsource (lib "eagle-import") (part "FOOTPRINT-BAKENEKO60"))
    )
    (comp (ref "U$25")
      (value "FOOTPRINT-DIMS-GH60")
      (footprint "eagle-import:FOOTPRINT-DIMS-GH60")
      (libsource (lib "eagle-import") (part "FOOTPRINT-DIMS-GH60"))
    )
    (comp (ref "X1")
      (value "MICROMOD-2222-C")
      (footprint "eagle-import:M.2-CONNECTOR-E")
      (libsource (lib "eagle-import") (part "MICROMOD-2222-C"))
    )
  )
  (nets
    (net (code "1") (name "52") (class "Default")
      (node (ref "J-52") (pin "2") (pinfunction "2_2") (pintype "passive"))
      (node (ref "X1") (pin "52") (pinfunction "AUD_LRCLK_52") (pintype "bidirectional"))
    )
    (net (code "2") (name "63") (class "Default")
      (node (ref "J-63") (pin "1") (pinfunction "1_1") (pintype "passive"))
      (node (ref "X1") (pin "63") (pinfunction "G10/ADC_D+/CAM_VSYNC_63") (pintype "bidirectional"))
    )
    (net (code "3") (name "BOOT") (class "Default")
      (node (ref "D80") (pin "3") (pinfunction "C_3") (pintype "passive"))
      (node (ref "J-BOOT") (pin "1") (pinfunction "1_1") (pintype "passive"))
      (node (ref "R9") (pin "1") (pinfunction "1_1") (pintype "passive"))
      (node (ref "S3") (pin "3") (pinfunction "2_3") (pintype "passive"))
      (node (ref "S3") (pin "4") (pinfunction "2_4") (pintype "passive"))
      (node (ref "S4") (pin "3") (pinfunction "2_3") (pintype "passive"))
      (node (ref "S4") (pin "4") (pinfunction "2_4") (pintype "passive"))
    )
    (net (code "4") (name "D+") (class "Default")
      (node (ref "ESD") (pin "P$1") (pinfunction "P$1_P$1") (pintype "bidirectional"))
      (node (ref "ESD") (pin "P$6") (pinfunction "P$6_P$6") (pintype "bidirectional"))
      (node (ref "J-UBS") (pin "A6") (pinfunction "D+_A6") (pintype "bidirectional"))
      (node (ref "J-UBS") (pin "B6") (pinfunction "D+_B6") (pintype "bidirectional"))
      (node (ref "J-UDB") (pin "3") (pinfunction "D+_3") (pintype "passive"))
      (node (ref "X1") (pin "3") (pinfunction "USB_D+_3") (pintype "bidirectional"))
    )
    (net (code "5") (name "D-") (class "Default")
      (node (ref "ESD") (pin "P$3") (pinfunction "P$3_P$3") (pintype "bidirectional"))
      (node (ref "ESD") (pin "P$4") (pinfunction "P$4_P$4") (pintype "bidirectional"))
      (node (ref "J-UBS") (pin "A7") (pinfunction "D-_A7") (pintype "bidirectional"))
      (node (ref "J-UBS") (pin "B7") (pinfunction "D-_B7") (pintype "bidirectional"))
      (node (ref "J-UDB") (pin "2") (pinfunction "D-_2") (pintype "passive"))
      (node (ref "X1") (pin "5") (pinfunction "USB_D-_5") (pintype "bidirectional"))
    )
    (net (code "6") (name "EE_CS") (class "Default")
      (node (ref "M1") (pin "1") (pinfunction "~{CS}_1") (pintype "bidirectional"))
      (node (ref "X1") (pin "55") (pinfunction "SPI_~{CS}_55") (pintype "bidirectional"))
    )
    (net (code "7") (name "GND") (class "Default")
      (node (ref "74AH") (pin "1") (pinfunction "~{OE}_1") (pintype "input"))
      (node (ref "74AH") (pin "3") (pinfunction "3_GND_3") (pintype "power_in"))
      (node (ref "C01") (pin "2") (pinfunction "2_2") (pintype "passive"))
      (node (ref "C02") (pin "2") (pinfunction "2_2") (pintype "passive"))
      (node (ref "C03") (pin "2") (pinfunction "2_2") (pintype "passive"))
      (node (ref "C04") (pin "2") (pinfunction "2_2") (pintype "passive"))
      (node (ref "C05") (pin "2") (pinfunction "2_2") (pintype "passive"))
      (node (ref "C06") (pin "2") (pinfunction "2_2") (pintype "passive"))
      (node (ref "C07") (pin "2") (pinfunction "2_2") (pintype "passive"))
      (node (ref "C08") (pin "2") (pinfunction "2_2") (pintype "passive"))
      (node (ref "C09") (pin "2") (pinfunction "2_2") (pintype "passive"))
      (node (ref "C10") (pin "2") (pinfunction "2_2") (pintype "passive"))
      (node (ref "C11") (pin "2") (pinfunction "2_2") (pintype "passive"))
      (node (ref "C12") (pin "2") (pinfunction "2_2") (pintype "passive"))
      (node (ref "C13") (pin "2") (pinfunction "2_2") (pintype "passive"))
      (node (ref "C14") (pin "2") (pinfunction "2_2") (pintype "passive"))
      (node (ref "ESD") (pin "P$2") (pinfunction "P$2_P$2") (pintype "bidirectional"))
      (node (ref "H5") (pin "1") (pinfunction "1_1") (pintype "bidirectional"))
      (node (ref "J-52") (pin "1") (pinfunction "1_1") (pintype "passive"))
      (node (ref "J-BOOT") (pin "2") (pinfunction "2_2") (pintype "passive"))
      (node (ref "J-LED") (pin "1") (pinfunction "1_1") (pintype "passive"))
      (node (ref "J-UBS") (pin "GND") (pinfunction "GND_GND") (pintype "bidirectional"))
      (node (ref "J-UBS") (pin "GND2") (pinfunction "GND_GND2") (pintype "bidirectional"))
      (node (ref "J-UDB") (pin "4") (pinfunction "GND_4") (pintype "power_in"))
      (node (ref "LED-5") (pin "3-GND") (pinfunction "3_GND_3-GND") (pintype "power_in"))
      (node (ref "LED-6") (pin "3-GND") (pinfunction "3_GND_3-GND") (pintype "power_in"))
      (node (ref "LED-7") (pin "3-GND") (pinfunction "3_GND_3-GND") (pintype "power_in"))
      (node (ref "LED-8") (pin "3-GND") (pinfunction "3_GND_3-GND") (pintype "power_in"))
      (node (ref "LED-CL") (pin "3-GND") (pinfunction "3_GND_3-GND") (pintype "power_in"))
      (node (ref "LM1117") (pin "1") (pinfunction "ADJ_1") (pintype "input"))
      (node (ref "M1") (pin "4") (pinfunction "GND_4") (pintype "bidirectional"))
      (node (ref "R1") (pin "2") (pinfunction "2_2") (pintype "passive"))
      (node (ref "R2") (pin "2") (pinfunction "2_2") (pintype "passive"))
      (node (ref "R4") (pin "1") (pinfunction "1_1") (pintype "passive"))
      (node (ref "R5") (pin "1") (pinfunction "1_1") (pintype "passive"))
      (node (ref "R8") (pin "1") (pinfunction "1_1") (pintype "passive"))
      (node (ref "S1") (pin "1") (pinfunction "1_1") (pintype "passive"))
      (node (ref "S2") (pin "1") (pinfunction "1_1") (pintype "passive"))
      (node (ref "S3") (pin "1") (pinfunction "1_1") (pintype "passive"))
      (node (ref "S3") (pin "2") (pinfunction "1_2") (pintype "passive"))
      (node (ref "S4") (pin "1") (pinfunction "1_1") (pintype "passive"))
      (node (ref "S4") (pin "2") (pinfunction "1_2") (pintype "passive"))
      (node (ref "TVS") (pin "P$2") (pinfunction "2_P$2") (pintype "passive"))
      (node (ref "X1") (pin "1") (pinfunction "GND_1") (pintype "bidirectional"))
      (node (ref "X1") (pin "33") (pinfunction "GND_33") (pintype "bidirectional"))
      (node (ref "X1") (pin "36") (pinfunction "GND_36") (pintype "bidirectional"))
      (node (ref "X1") (pin "39") (pinfunction "GND_39") (pintype "bidirectional"))
      (node (ref "X1") (pin "45") (pinfunction "GND_45") (pintype "bidirectional"))
      (node (ref "X1") (pin "7") (pinfunction "GND_7") (pintype "bidirectional"))
      (node (ref "X1") (pin "75") (pinfunction "GND_75") (pintype "bidirectional"))
    )
    (net (code "8") (name "GROUND") (class "Default")
      (node (ref "C06") (pin "1") (pinfunction "1_1") (pintype "passive"))
      (node (ref "J-UBS") (pin "SHLD1") (pinfunction "SHLD_SHLD1") (pintype "bidirectional"))
      (node (ref "J-UBS") (pin "SHLD2") (pinfunction "SHLD_SHLD2") (pintype "bidirectional"))
      (node (ref "J-UBS") (pin "SHLD3") (pinfunction "SHLD_SHLD3") (pintype "bidirectional"))
      (node (ref "J-UBS") (pin "SHLD4") (pinfunction "SHLD_SHLD4") (pintype "bidirectional"))
      (node (ref "J-UBS") (pin "SHLD5") (pinfunction "SHLD_SHLD5") (pintype "bidirectional"))
      (node (ref "J-UBS") (pin "SHLD6") (pinfunction "SHLD_SHLD6") (pintype "bidirectional"))
      (node (ref "J-UBS") (pin "SHLD7") (pinfunction "SHLD_SHLD7") (pintype "bidirectional"))
      (node (ref "J-UBS") (pin "SHLD8") (pinfunction "SHLD_SHLD8") (pintype "bidirectional"))
      (node (ref "JP-GND") (pin "2") (pinfunction "2_2") (pintype "passive"))
      (node (ref "R5") (pin "2") (pinfunction "2_2") (pintype "passive"))
    )
    (net (code "9") (name "LED") (class "Default")
      (node (ref "R6") (pin "2") (pinfunction "2_2") (pintype "passive"))
      (node (ref "X1") (pin "32") (pinfunction "PWM0_32") (pintype "bidirectional"))
    )
    (net (code "10") (name "MISO") (class "Default")
      (node (ref "M1") (pin "2") (pinfunction "DO_2") (pintype "bidirectional"))
      (node (ref "X1") (pin "61") (pinfunction "SPI_SDI_61") (pintype "bidirectional"))
    )
    (net (code "11") (name "MOSI") (class "Default")
      (node (ref "M1") (pin "5") (pinfunction "DIO_5") (pintype "bidirectional"))
      (node (ref "X1") (pin "59") (pinfunction "SPI_SDO_59") (pintype "bidirectional"))
    )
    (net (code "12") (name "MX0") (class "Default")
      (node (ref "D01") (pin "C") (pinfunction "C_C") (pintype "passive"))
      (node (ref "D09") (pin "C") (pinfunction "C_C") (pintype "passive"))
      (node (ref "D15") (pin "C") (pinfunction "C_C") (pintype "passive"))
      (node (ref "D23") (pin "C") (pinfunction "C_C") (pintype "passive"))
      (node (ref "D29") (pin "C") (pinfunction "C_C") (pintype "passive"))
      (node (ref "D37") (pin "C") (pinfunction "C_C") (pintype "passive"))
      (node (ref "D42") (pin "C") (pinfunction "C_C") (pintype "passive"))
      (node (ref "D50") (pin "C") (pinfunction "C_C") (pintype "passive"))
      (node (ref "D55") (pin "C") (pinfunction "C_C") (pintype "passive"))
      (node (ref "X1") (pin "47") (pinfunction "PWM1_47") (pintype "bidirectional"))
    )
    (net (code "13") (name "MX1") (class "Default")
      (node (ref "D02") (pin "C") (pinfunction "C_C") (pintype "passive"))
      (node (ref "D10") (pin "C") (pinfunction "C_C") (pintype "passive"))
      (node (ref "D16") (pin "C") (pinfunction "C_C") (pintype "passive"))
      (node (ref "D24") (pin "C") (pinfunction "C_C") (pintype "passive"))
      (node (ref "D30") (pin "C") (pinfunction "C_C") (pintype "passive"))
      (node (ref "D38") (pin "C") (pinfunction "C_C") (pintype "passive"))
      (node (ref "D43") (pin "C") (pinfunction "C_C") (pintype "passive"))
      (node (ref "D51") (pin "C") (pinfunction "C_C") (pintype "passive"))
      (node (ref "D56") (pin "C") (pinfunction "C_C") (pintype "passive"))
      (node (ref "X1") (pin "19") (pinfunction "RX1_19") (pintype "bidirectional"))
    )
    (net (code "14") (name "MX2") (class "Default")
      (node (ref "D03") (pin "C") (pinfunction "C_C") (pintype "passive"))
      (node (ref "D11") (pin "C") (pinfunction "C_C") (pintype "passive"))
      (node (ref "D17") (pin "C") (pinfunction "C_C") (pintype "passive"))
      (node (ref "D25") (pin "C") (pinfunction "C_C") (pintype "passive"))
      (node (ref "D31") (pin "C") (pinfunction "C_C") (pintype "passive"))
      (node (ref "D39") (pin "C") (pinfunction "C_C") (pintype "passive"))
      (node (ref "D44") (pin "C") (pinfunction "C_C") (pintype "passive"))
      (node (ref "D52") (pin "C") (pinfunction "C_C") (pintype "passive"))
      (node (ref "D57") (pin "C") (pinfunction "C_C") (pintype "passive"))
      (node (ref "X1") (pin "17") (pinfunction "TX1_17") (pintype "bidirectional"))
    )
    (net (code "15") (name "MX3") (class "Default")
      (node (ref "D04") (pin "C") (pinfunction "C_C") (pintype "passive"))
      (node (ref "D12") (pin "C") (pinfunction "C_C") (pintype "passive"))
      (node (ref "D18") (pin "C") (pinfunction "C_C") (pintype "passive"))
      (node (ref "D26") (pin "C") (pinfunction "C_C") (pintype "passive"))
      (node (ref "D32") (pin "C") (pinfunction "C_C") (pintype "passive"))
      (node (ref "D40") (pin "C") (pinfunction "C_C") (pintype "passive"))
      (node (ref "D45") (pin "C") (pinfunction "C_C") (pintype "passive"))
      (node (ref "D53") (pin "C") (pinfunction "C_C") (pintype "passive"))
      (node (ref "D58") (pin "C") (pinfunction "C_C") (pintype "passive"))
      (node (ref "X1") (pin "18") (pinfunction "D1/CAM_TRIG_18") (pintype "bidirectional"))
    )
    (net (code "16") (name "MX4") (class "Default")
      (node (ref "D05") (pin "C") (pinfunction "C_C") (pintype "passive"))
      (node (ref "D13") (pin "C") (pinfunction "C_C") (pintype "passive"))
      (node (ref "D19") (pin "C") (pinfunction "C_C") (pintype "passive"))
      (node (ref "D27") (pin "C") (pinfunction "C_C") (pintype "passive"))
      (node (ref "D33") (pin "C") (pinfunction "C_C") (pintype "passive"))
      (node (ref "D46") (pin "C") (pinfunction "C_C") (pintype "passive"))
      (node (ref "D59") (pin "C") (pinfunction "C_C") (pintype "passive"))
      (node (ref "D63") (pin "C") (pinfunction "C_C") (pintype "passive"))
      (node (ref "D64") (pin "C") (pinfunction "C_C") (pintype "passive"))
      (node (ref "X1") (pin "16") (pinfunction "I2C_~{INT}_16") (pintype "bidirectional"))
    )
    (net (code "17") (name "MX5") (class "Default")
      (node (ref "D06") (pin "C") (pinfunction "C_C") (pintype "passive"))
      (node (ref "D20") (pin "C") (pinfunction "C_C") (pintype "passive"))
      (node (ref "D34") (pin "C") (pinfunction "C_C") (pintype "passive"))
      (node (ref "D47") (pin "C") (pinfunction "C_C") (pintype "passive"))
      (node (ref "D54") (pin "C") (pinfunction "C_C") (pintype "passive"))
      (node (ref "D60") (pin "C") (pinfunction "C_C") (pintype "passive"))
      (node (ref "D65") (pin "C") (pinfunction "C_C") (pintype "passive"))
      (node (ref "D66") (pin "C") (pinfunction "C_C") (pintype "passive"))
      (node (ref "D67") (pin "C") (pinfunction "C_C") (pintype "passive"))
      (node (ref "X1") (pin "14") (pinfunction "I2C_SCL_14") (pintype "bidirectional"))
    )
    (net (code "18") (name "MX6") (class "Default")
      (node (ref "D07") (pin "C") (pinfunction "C_C") (pintype "passive"))
      (node (ref "D14") (pin "C") (pinfunction "C_C") (pintype "passive"))
      (node (ref "D21") (pin "C") (pinfunction "C_C") (pintype "passive"))
      (node (ref "D28") (pin "C") (pinfunction "C_C") (pintype "passive"))
      (node (ref "D35") (pin "C") (pinfunction "C_C") (pintype "passive"))
      (node (ref "D41") (pin "C") (pinfunction "C_C") (pintype "passive"))
      (node (ref "D48") (pin "C") (pinfunction "C_C") (pintype "passive"))
      (node (ref "D61") (pin "C") (pinfunction "C_C") (pintype "passive"))
      (node (ref "X1") (pin "12") (pinfunction "I2C_SDA_12") (pintype "bidirectional"))
    )
    (net (code "19") (name "MX7") (class "Default")
      (node (ref "D08") (pin "C") (pinfunction "C_C") (pintype "passive"))
      (node (ref "D22") (pin "C") (pinfunction "C_C") (pintype "passive"))
      (node (ref "D36") (pin "C") (pinfunction "C_C") (pintype "passive"))
      (node (ref "D49") (pin "C") (pinfunction "C_C") (pintype "passive"))
      (node (ref "D62") (pin "C") (pinfunction "C_C") (pintype "passive"))
      (node (ref "X1") (pin "10") (pinfunction "D0_10") (pintype "bidirectional"))
    )
    (net (code "20") (name "MY0") (class "Default")
      (node (ref "S_1") (pin "2@1") (pinfunction "S_2@1") (pintype "passive"))
      (node (ref "S_1") (pin "2@2") (pinfunction "S_2@2") (pintype "passive"))
      (node (ref "S_2") (pin "2@1") (pinfunction "S_2@1") (pintype "passive"))
      (node (ref "S_2") (pin "2@2") (pinfunction "S_2@2") (pintype "passive"))
      (node (ref "S_3") (pin "2@1") (pinfunction "S_2@1") (pintype "passive"))
      (node (ref "S_3") (pin "2@2") (pinfunction "S_2@2") (pintype "passive"))
      (node (ref "S_4") (pin "2@1") (pinfunction "S_2@1") (pintype "passive"))
      (node (ref "S_4") (pin "2@2") (pinfunction "S_2@2") (pintype "passive"))
      (node (ref "S_5") (pin "2@1") (pinfunction "S_2@1") (pintype "passive"))
      (node (ref "S_5") (pin "2@2") (pinfunction "S_2@2") (pintype "passive"))
      (node (ref "S_6") (pin "2@1") (pinfunction "S_2@1") (pintype "passive"))
      (node (ref "S_6") (pin "2@2") (pinfunction "S_2@2") (pintype "passive"))
      (node (ref "S_7") (pin "2@1") (pinfunction "S_2@1") (pintype "passive"))
      (node (ref "S_7") (pin "2@2") (pinfunction "S_2@2") (pintype "passive"))
      (node (ref "S_ESC") (pin "2@1") (pinfunction "S_2@1") (pintype "passive"))
      (node (ref "S_ESC") (pin "2@2") (pinfunction "S_2@2") (pintype "passive"))
      (node (ref "X1") (pin "56") (pinfunction "AUD_OUT/CAM_MCLK_56") (pintype "bidirectional"))
    )
    (net (code "21") (name "MY1") (class "Default")
      (node (ref "S_E") (pin "2@1") (pinfunction "S_2@1") (pintype "passive"))
      (node (ref "S_E") (pin "2@2") (pinfunction "S_2@2") (pintype "passive"))
      (node (ref "S_Q") (pin "2@1") (pinfunction "S_2@1") (pintype "passive"))
      (node (ref "S_Q") (pin "2@2") (pinfunction "S_2@2") (pintype "passive"))
      (node (ref "S_R") (pin "2@1") (pinfunction "S_2@1") (pintype "passive"))
      (node (ref "S_R") (pin "2@2") (pinfunction "S_2@2") (pintype "passive"))
      (node (ref "S_T") (pin "2@1") (pinfunction "S_2@1") (pintype "passive"))
      (node (ref "S_T") (pin "2@2") (pinfunction "S_2@2") (pintype "passive"))
      (node (ref "S_TAB") (pin "2@1") (pinfunction "S_2@1") (pintype "passive"))
      (node (ref "S_TAB") (pin "2@2") (pinfunction "S_2@2") (pintype "passive"))
      (node (ref "S_U") (pin "2@1") (pinfunction "S_2@1") (pintype "passive"))
      (node (ref "S_U") (pin "2@2") (pinfunction "S_2@2") (pintype "passive"))
      (node (ref "S_W") (pin "2@1") (pinfunction "S_2@1") (pintype "passive"))
      (node (ref "S_W") (pin "2@2") (pinfunction "S_2@2") (pintype "passive"))
      (node (ref "S_Y") (pin "2@1") (pinfunction "S_2@1") (pintype "passive"))
      (node (ref "S_Y") (pin "2@2") (pinfunction "S_2@2") (pintype "passive"))
      (node (ref "X1") (pin "54") (pinfunction "AUD_IN/CAM_PCLK_54") (pintype "bidirectional"))
    )
    (net (code "22") (name "MY2") (class "Default")
      (node (ref "S_A") (pin "2@1") (pinfunction "S_2@1") (pintype "passive"))
      (node (ref "S_A") (pin "2@2") (pinfunction "S_2@2") (pintype "passive"))
      (node (ref "S_CAPS") (pin "2@1") (pinfunction "S_2@1") (pintype "passive"))
      (node (ref "S_CAPS") (pin "2@2") (pinfunction "S_2@2") (pintype "passive"))
      (node (ref "S_CAPS2") (pin "1") (pinfunction "P_1") (pintype "passive"))
      (node (ref "S_D") (pin "2@1") (pinfunction "S_2@1") (pintype "passive"))
      (node (ref "S_D") (pin "2@2") (pinfunction "S_2@2") (pintype "passive"))
      (node (ref "S_F") (pin "2@1") (pinfunction "S_2@1") (pintype "passive"))
      (node (ref "S_F") (pin "2@2") (pinfunction "S_2@2") (pintype "passive"))
      (node (ref "S_G") (pin "2@1") (pinfunction "S_2@1") (pintype "passive"))
      (node (ref "S_G") (pin "2@2") (pinfunction "S_2@2") (pintype "passive"))
      (node (ref "S_H") (pin "2@1") (pinfunction "S_2@1") (pintype "passive"))
      (node (ref "S_H") (pin "2@2") (pinfunction "S_2@2") (pintype "passive"))
      (node (ref "S_J") (pin "2@1") (pinfunction "S_2@1") (pintype "passive"))
      (node (ref "S_J") (pin "2@2") (pinfunction "S_2@2") (pintype "passive"))
      (node (ref "S_S") (pin "2@1") (pinfunction "S_2@1") (pintype "passive"))
      (node (ref "S_S") (pin "2@2") (pinfunction "S_2@2") (pintype "passive"))
      (node (ref "X1") (pin "50") (pinfunction "AUD_BCLK_50") (pintype "bidirectional"))
    )
    (net (code "23") (name "MY3") (class "Default")
      (node (ref "S_B") (pin "2@1") (pinfunction "S_2@1") (pintype "passive"))
      (node (ref "S_B") (pin "2@2") (pinfunction "S_2@2") (pintype "passive"))
      (node (ref "S_C") (pin "2@1") (pinfunction "S_2@1") (pintype "passive"))
      (node (ref "S_C") (pin "2@2") (pinfunction "S_2@2") (pintype "passive"))
      (node (ref "S_LSFT") (pin "2@1") (pinfunction "S_2@1") (pintype "passive"))
      (node (ref "S_LSFT") (pin "2@2") (pinfunction "S_2@2") (pintype "passive"))
      (node (ref "S_LSFT2") (pin "2@1") (pinfunction "S_2@1") (pintype "passive"))
      (node (ref "S_LSFT2") (pin "2@2") (pinfunction "S_2@2") (pintype "passive"))
      (node (ref "S_N") (pin "2@1") (pinfunction "S_2@1") (pintype "passive"))
      (node (ref "S_N") (pin "2@2") (pinfunction "S_2@2") (pintype "passive"))
      (node (ref "S_NUBS") (pin "2@1") (pinfunction "S_2@1") (pintype "passive"))
      (node (ref "S_NUBS") (pin "2@2") (pinfunction "S_2@2") (pintype "passive"))
      (node (ref "S_V") (pin "2@1") (pinfunction "S_2@1") (pintype "passive"))
      (node (ref "S_V") (pin "2@2") (pinfunction "S_2@2") (pintype "passive"))
      (node (ref "S_X") (pin "2@1") (pinfunction "S_2@1") (pintype "passive"))
      (node (ref "S_X") (pin "2@2") (pinfunction "S_2@2") (pintype "passive"))
      (node (ref "S_Z") (pin "2@1") (pinfunction "S_2@1") (pintype "passive"))
      (node (ref "S_Z") (pin "2@2") (pinfunction "S_2@2") (pintype "passive"))
      (node (ref "X1") (pin "46") (pinfunction "G3/BUS3_46") (pintype "bidirectional"))
    )
    (net (code "24") (name "MY4") (class "Default")
      (node (ref "S_APP") (pin "2@1") (pinfunction "S_2@1") (pintype "passive"))
      (node (ref "S_APP") (pin "2@2") (pinfunction "S_2@2") (pintype "passive"))
      (node (ref "S_FN1") (pin "2@1") (pinfunction "S_2@1") (pintype "passive"))
      (node (ref "S_FN1") (pin "2@2") (pinfunction "S_2@2") (pintype "passive"))
      (node (ref "S_LALT") (pin "2@1") (pinfunction "S_2@1") (pintype "passive"))
      (node (ref "S_LALT") (pin "2@2") (pinfunction "S_2@2") (pintype "passive"))
      (node (ref "S_LCTL") (pin "2@1") (pinfunction "S_2@1") (pintype "passive"))
      (node (ref "S_LCTL") (pin "2@2") (pinfunction "S_2@2") (pintype "passive"))
      (node (ref "S_LGUI") (pin "2@1") (pinfunction "S_2@1") (pintype "passive"))
      (node (ref "S_LGUI") (pin "2@2") (pinfunction "S_2@2") (pintype "passive"))
      (node (ref "S_RALT") (pin "2@1") (pinfunction "S_2@1") (pintype "passive"))
      (node (ref "S_RALT") (pin "2@2") (pinfunction "S_2@2") (pintype "passive"))
      (node (ref "S_RCTL") (pin "2@1") (pinfunction "S_2@1") (pintype "passive"))
      (node (ref "S_RCTL") (pin "2@2") (pinfunction "S_2@2") (pintype "passive"))
      (node (ref "S_SPC") (pin "2@1") (pinfunction "S_2@1") (pintype "passive"))
      (node (ref "S_SPC") (pin "2@2") (pinfunction "S_2@2") (pintype "passive"))
      (node (ref "X1") (pin "44") (pinfunction "G2/BUS2_44") (pintype "bidirectional"))
    )
    (net (code "25") (name "MY5") (class "Default")
      (node (ref "DIP-SW") (pin "8") (pinfunction "8_8") (pintype "passive"))
      (node (ref "S_0") (pin "2@1") (pinfunction "S_2@1") (pintype "passive"))
      (node (ref "S_0") (pin "2@2") (pinfunction "S_2@2") (pintype "passive"))
      (node (ref "S_8") (pin "2@1") (pinfunction "S_2@1") (pintype "passive"))
      (node (ref "S_8") (pin "2@2") (pinfunction "S_2@2") (pintype "passive"))
      (node (ref "S_9") (pin "2@1") (pinfunction "S_2@1") (pintype "passive"))
      (node (ref "S_9") (pin "2@2") (pinfunction "S_2@2") (pintype "passive"))
      (node (ref "S_BSPC") (pin "2@1") (pinfunction "S_2@1") (pintype "passive"))
      (node (ref "S_BSPC") (pin "2@2") (pinfunction "S_2@2") (pintype "passive"))
      (node (ref "S_BSPC2") (pin "2") (pinfunction "S_2") (pintype "passive"))
      (node (ref "S_EQL") (pin "2@1") (pinfunction "S_2@1") (pintype "passive"))
      (node (ref "S_EQL") (pin "2@2") (pinfunction "S_2@2") (pintype "passive"))
      (node (ref "S_MINS") (pin "2@1") (pinfunction "S_2@1") (pintype "passive"))
      (node (ref "S_MINS") (pin "2@2") (pinfunction "S_2@2") (pintype "passive"))
      (node (ref "X1") (pin "42") (pinfunction "G1/BUS1_42") (pintype "bidirectional"))
    )
    (net (code "26") (name "MY6") (class "Default")
      (node (ref "DIP-SW") (pin "7") (pinfunction "7_7") (pintype "passive"))
      (node (ref "S_BSLS") (pin "2@1") (pinfunction "S_2@1") (pintype "passive"))
      (node (ref "S_BSLS") (pin "2@2") (pinfunction "S_2@2") (pintype "passive"))
      (node (ref "S_BSLS2") (pin "2@1") (pinfunction "S_2@1") (pintype "passive"))
      (node (ref "S_BSLS2") (pin "2@2") (pinfunction "S_2@2") (pintype "passive"))
      (node (ref "S_I") (pin "2@1") (pinfunction "S_2@1") (pintype "passive"))
      (node (ref "S_I") (pin "2@2") (pinfunction "S_2@2") (pintype "passive"))
      (node (ref "S_LBRC") (pin "2@1") (pinfunction "S_2@1") (pintype "passive"))
      (node (ref "S_LBRC") (pin "2@2") (pinfunction "S_2@2") (pintype "passive"))
      (node (ref "S_O") (pin "2@1") (pinfunction "S_2@1") (pintype "passive"))
      (node (ref "S_O") (pin "2@2") (pinfunction "S_2@2") (pintype "passive"))
      (node (ref "S_P") (pin "2@1") (pinfunction "S_2@1") (pintype "passive"))
      (node (ref "S_P") (pin "2@2") (pinfunction "S_2@2") (pintype "passive"))
      (node (ref "S_RBRC") (pin "2@1") (pinfunction "S_2@1") (pintype "passive"))
      (node (ref "S_RBRC") (pin "2@2") (pinfunction "S_2@2") (pintype "passive"))
      (node (ref "X1") (pin "40") (pinfunction "G0/BUS0_40") (pintype "bidirectional"))
    )
    (net (code "27") (name "MY7") (class "Default")
      (node (ref "DIP-SW") (pin "6") (pinfunction "6_6") (pintype "passive"))
      (node (ref "S_ENT") (pin "2@1") (pinfunction "S_2@1") (pintype "passive"))
      (node (ref "S_ENT") (pin "2@2") (pinfunction "S_2@2") (pintype "passive"))
      (node (ref "S_ENT2") (pin "2@1") (pinfunction "S_2@1") (pintype "passive"))
      (node (ref "S_ENT2") (pin "2@2") (pinfunction "S_2@2") (pintype "passive"))
      (node (ref "S_K") (pin "2@1") (pinfunction "S_2@1") (pintype "passive"))
      (node (ref "S_K") (pin "2@2") (pinfunction "S_2@2") (pintype "passive"))
      (node (ref "S_L") (pin "2@1") (pinfunction "S_2@1") (pintype "passive"))
      (node (ref "S_L") (pin "2@2") (pinfunction "S_2@2") (pintype "passive"))
      (node (ref "S_QUOT") (pin "2@1") (pinfunction "S_2@1") (pintype "passive"))
      (node (ref "S_QUOT") (pin "2@2") (pinfunction "S_2@2") (pintype "passive"))
      (node (ref "S_SCLN") (pin "2@1") (pinfunction "S_2@1") (pintype "passive"))
      (node (ref "S_SCLN") (pin "2@2") (pinfunction "S_2@2") (pintype "passive"))
      (node (ref "S_SPARE") (pin "2") (pinfunction "S_2") (pintype "passive"))
      (node (ref "X1") (pin "38") (pinfunction "A1_38") (pintype "bidirectional"))
    )
    (net (code "28") (name "MY8") (class "Default")
      (node (ref "S_COM") (pin "2@1") (pinfunction "S_2@1") (pintype "passive"))
      (node (ref "S_COM") (pin "2@2") (pinfunction "S_2@2") (pintype "passive"))
      (node (ref "S_DOT") (pin "2@1") (pinfunction "S_2@1") (pintype "passive"))
      (node (ref "S_DOT") (pin "2@2") (pinfunction "S_2@2") (pintype "passive"))
      (node (ref "S_FN") (pin "2") (pinfunction "S_2") (pintype "passive"))
      (node (ref "S_M") (pin "2@1") (pinfunction "S_2@1") (pintype "passive"))
      (node (ref "S_M") (pin "2@2") (pinfunction "S_2@2") (pintype "passive"))
      (node (ref "S_RSFT") (pin "2@1") (pinfunction "S_2@1") (pintype "passive"))
      (node (ref "S_RSFT") (pin "2@2") (pinfunction "S_2@2") (pintype "passive"))
      (node (ref "S_RSFT2") (pin "2") (pinfunction "S_2") (pintype "passive"))
      (node (ref "S_SLSH") (pin "2@1") (pinfunction "S_2@1") (pintype "passive"))
      (node (ref "S_SLSH") (pin "2@2") (pinfunction "S_2@2") (pintype "passive"))
      (node (ref "X1") (pin "34") (pinfunction "A0_34") (pintype "bidirectional"))
    )
    (net (code "29") (name "Net-(74AH-A_DIN)") (class "Default")
      (node (ref "74AH") (pin "2") (pinfunction "A_DIN_2") (pintype "input"))
      (node (ref "R6") (pin "1") (pinfunction "1_1") (pintype "passive"))
    )
    (net (code "30") (name "Net-(74AH-Y_DOUT)") (class "Default")
      (node (ref "74AH") (pin "4") (pinfunction "Y_DOUT_4") (pintype "output"))
      (node (ref "R7") (pin "2") (pinfunction "2_2") (pintype "passive"))
    )
    (net (code "31") (name "Net-(D01-PadA)") (class "Default")
      (node (ref "D01") (pin "A") (pinfunction "A_A") (pintype "passive"))
      (node (ref "S_ESC") (pin "1@1") (pinfunction "P_1@1") (pintype "passive"))
      (node (ref "S_ESC") (pin "1@2") (pinfunction "P_1@2") (pintype "passive"))
    )
    (net (code "32") (name "Net-(D02-PadA)") (class "Default")
      (node (ref "D02") (pin "A") (pinfunction "A_A") (pintype "passive"))
      (node (ref "S_1") (pin "1@1") (pinfunction "P_1@1") (pintype "passive"))
      (node (ref "S_1") (pin "1@2") (pinfunction "P_1@2") (pintype "passive"))
    )
    (net (code "33") (name "Net-(D03-PadA)") (class "Default")
      (node (ref "D03") (pin "A") (pinfunction "A_A") (pintype "passive"))
      (node (ref "S_2") (pin "1@1") (pinfunction "P_1@1") (pintype "passive"))
      (node (ref "S_2") (pin "1@2") (pinfunction "P_1@2") (pintype "passive"))
    )
    (net (code "34") (name "Net-(D04-PadA)") (class "Default")
      (node (ref "D04") (pin "A") (pinfunction "A_A") (pintype "passive"))
      (node (ref "S_3") (pin "1@1") (pinfunction "P_1@1") (pintype "passive"))
      (node (ref "S_3") (pin "1@2") (pinfunction "P_1@2") (pintype "passive"))
    )
    (net (code "35") (name "Net-(D05-PadA)") (class "Default")
      (node (ref "D05") (pin "A") (pinfunction "A_A") (pintype "passive"))
      (node (ref "S_4") (pin "1@1") (pinfunction "P_1@1") (pintype "passive"))
      (node (ref "S_4") (pin "1@2") (pinfunction "P_1@2") (pintype "passive"))
    )
    (net (code "36") (name "Net-(D06-PadA)") (class "Default")
      (node (ref "D06") (pin "A") (pinfunction "A_A") (pintype "passive"))
      (node (ref "S_5") (pin "1@1") (pinfunction "P_1@1") (pintype "passive"))
      (node (ref "S_5") (pin "1@2") (pinfunction "P_1@2") (pintype "passive"))
    )
    (net (code "37") (name "Net-(D07-PadA)") (class "Default")
      (node (ref "D07") (pin "A") (pinfunction "A_A") (pintype "passive"))
      (node (ref "S_6") (pin "1@1") (pinfunction "P_1@1") (pintype "passive"))
      (node (ref "S_6") (pin "1@2") (pinfunction "P_1@2") (pintype "passive"))
    )
    (net (code "38") (name "Net-(D08-PadA)") (class "Default")
      (node (ref "D08") (pin "A") (pinfunction "A_A") (pintype "passive"))
      (node (ref "S_7") (pin "1@1") (pinfunction "P_1@1") (pintype "passive"))
      (node (ref "S_7") (pin "1@2") (pinfunction "P_1@2") (pintype "passive"))
    )
    (net (code "39") (name "Net-(D09-PadA)") (class "Default")
      (node (ref "D09") (pin "A") (pinfunction "A_A") (pintype "passive"))
      (node (ref "S_8") (pin "1@1") (pinfunction "P_1@1") (pintype "passive"))
      (node (ref "S_8") (pin "1@2") (pinfunction "P_1@2") (pintype "passive"))
    )
    (net (code "40") (name "Net-(D10-PadA)") (class "Default")
      (node (ref "D10") (pin "A") (pinfunction "A_A") (pintype "passive"))
      (node (ref "S_9") (pin "1@1") (pinfunction "P_1@1") (pintype "passive"))
      (node (ref "S_9") (pin "1@2") (pinfunction "P_1@2") (pintype "passive"))
    )
    (net (code "41") (name "Net-(D11-PadA)") (class "Default")
      (node (ref "D11") (pin "A") (pinfunction "A_A") (pintype "passive"))
      (node (ref "S_0") (pin "1@1") (pinfunction "P_1@1") (pintype "passive"))
      (node (ref "S_0") (pin "1@2") (pinfunction "P_1@2") (pintype "passive"))
    )
    (net (code "42") (name "Net-(D12-PadA)") (class "Default")
      (node (ref "D12") (pin "A") (pinfunction "A_A") (pintype "passive"))
      (node (ref "S_MINS") (pin "1@1") (pinfunction "P_1@1") (pintype "passive"))
      (node (ref "S_MINS") (pin "1@2") (pinfunction "P_1@2") (pintype "passive"))
    )
    (net (code "43") (name "Net-(D13-PadA)") (class "Default")
      (node (ref "D13") (pin "A") (pinfunction "A_A") (pintype "passive"))
      (node (ref "S_EQL") (pin "1@1") (pinfunction "P_1@1") (pintype "passive"))
      (node (ref "S_EQL") (pin "1@2") (pinfunction "P_1@2") (pintype "passive"))
    )
    (net (code "44") (name "Net-(D15-PadA)") (class "Default")
      (node (ref "D15") (pin "A") (pinfunction "A_A") (pintype "passive"))
      (node (ref "S_TAB") (pin "1@1") (pinfunction "P_1@1") (pintype "passive"))
      (node (ref "S_TAB") (pin "1@2") (pinfunction "P_1@2") (pintype "passive"))
    )
    (net (code "45") (name "Net-(D16-PadA)") (class "Default")
      (node (ref "D16") (pin "A") (pinfunction "A_A") (pintype "passive"))
      (node (ref "S_Q") (pin "1@1") (pinfunction "P_1@1") (pintype "passive"))
      (node (ref "S_Q") (pin "1@2") (pinfunction "P_1@2") (pintype "passive"))
    )
    (net (code "46") (name "Net-(D17-PadA)") (class "Default")
      (node (ref "D17") (pin "A") (pinfunction "A_A") (pintype "passive"))
      (node (ref "S_W") (pin "1@1") (pinfunction "P_1@1") (pintype "passive"))
      (node (ref "S_W") (pin "1@2") (pinfunction "P_1@2") (pintype "passive"))
    )
    (net (code "47") (name "Net-(D18-PadA)") (class "Default")
      (node (ref "D18") (pin "A") (pinfunction "A_A") (pintype "passive"))
      (node (ref "S_E") (pin "1@1") (pinfunction "P_1@1") (pintype "passive"))
      (node (ref "S_E") (pin "1@2") (pinfunction "P_1@2") (pintype "passive"))
    )
    (net (code "48") (name "Net-(D19-PadA)") (class "Default")
      (node (ref "D19") (pin "A") (pinfunction "A_A") (pintype "passive"))
      (node (ref "S_R") (pin "1@1") (pinfunction "P_1@1") (pintype "passive"))
      (node (ref "S_R") (pin "1@2") (pinfunction "P_1@2") (pintype "passive"))
    )
    (net (code "49") (name "Net-(D20-PadA)") (class "Default")
      (node (ref "D20") (pin "A") (pinfunction "A_A") (pintype "passive"))
      (node (ref "S_T") (pin "1@1") (pinfunction "P_1@1") (pintype "passive"))
      (node (ref "S_T") (pin "1@2") (pinfunction "P_1@2") (pintype "passive"))
    )
    (net (code "50") (name "Net-(D21-PadA)") (class "Default")
      (node (ref "D21") (pin "A") (pinfunction "A_A") (pintype "passive"))
      (node (ref "S_Y") (pin "1@1") (pinfunction "P_1@1") (pintype "passive"))
      (node (ref "S_Y") (pin "1@2") (pinfunction "P_1@2") (pintype "passive"))
    )
    (net (code "51") (name "Net-(D22-PadA)") (class "Default")
      (node (ref "D22") (pin "A") (pinfunction "A_A") (pintype "passive"))
      (node (ref "S_U") (pin "1@1") (pinfunction "P_1@1") (pintype "passive"))
      (node (ref "S_U") (pin "1@2") (pinfunction "P_1@2") (pintype "passive"))
    )
    (net (code "52") (name "Net-(D23-PadA)") (class "Default")
      (node (ref "D23") (pin "A") (pinfunction "A_A") (pintype "passive"))
      (node (ref "S_I") (pin "1@1") (pinfunction "P_1@1") (pintype "passive"))
      (node (ref "S_I") (pin "1@2") (pinfunction "P_1@2") (pintype "passive"))
    )
    (net (code "53") (name "Net-(D24-PadA)") (class "Default")
      (node (ref "D24") (pin "A") (pinfunction "A_A") (pintype "passive"))
      (node (ref "S_O") (pin "1@1") (pinfunction "P_1@1") (pintype "passive"))
      (node (ref "S_O") (pin "1@2") (pinfunction "P_1@2") (pintype "passive"))
    )
    (net (code "54") (name "Net-(D25-PadA)") (class "Default")
      (node (ref "D25") (pin "A") (pinfunction "A_A") (pintype "passive"))
      (node (ref "S_P") (pin "1@1") (pinfunction "P_1@1") (pintype "passive"))
      (node (ref "S_P") (pin "1@2") (pinfunction "P_1@2") (pintype "passive"))
    )
    (net (code "55") (name "Net-(D26-PadA)") (class "Default")
      (node (ref "D26") (pin "A") (pinfunction "A_A") (pintype "passive"))
      (node (ref "S_LBRC") (pin "1@1") (pinfunction "P_1@1") (pintype "passive"))
      (node (ref "S_LBRC") (pin "1@2") (pinfunction "P_1@2") (pintype "passive"))
    )
    (net (code "56") (name "Net-(D27-PadA)") (class "Default")
      (node (ref "D27") (pin "A") (pinfunction "A_A") (pintype "passive"))
      (node (ref "S_RBRC") (pin "1@1") (pinfunction "P_1@1") (pintype "passive"))
      (node (ref "S_RBRC") (pin "1@2") (pinfunction "P_1@2") (pintype "passive"))
    )
    (net (code "57") (name "Net-(D28-PadA)") (class "Default")
      (node (ref "D28") (pin "A") (pinfunction "A_A") (pintype "passive"))
      (node (ref "S_BSLS") (pin "1@1") (pinfunction "P_1@1") (pintype "passive"))
      (node (ref "S_BSLS") (pin "1@2") (pinfunction "P_1@2") (pintype "passive"))
      (node (ref "S_BSLS2") (pin "1@1") (pinfunction "P_1@1") (pintype "passive"))
      (node (ref "S_BSLS2") (pin "1@2") (pinfunction "P_1@2") (pintype "passive"))
    )
    (net (code "58") (name "Net-(D30-PadA)") (class "Default")
      (node (ref "D30") (pin "A") (pinfunction "A_A") (pintype "passive"))
      (node (ref "S_A") (pin "1@1") (pinfunction "P_1@1") (pintype "passive"))
      (node (ref "S_A") (pin "1@2") (pinfunction "P_1@2") (pintype "passive"))
    )
    (net (code "59") (name "Net-(D31-PadA)") (class "Default")
      (node (ref "D31") (pin "A") (pinfunction "A_A") (pintype "passive"))
      (node (ref "S_S") (pin "1@1") (pinfunction "P_1@1") (pintype "passive"))
      (node (ref "S_S") (pin "1@2") (pinfunction "P_1@2") (pintype "passive"))
    )
    (net (code "60") (name "Net-(D32-PadA)") (class "Default")
      (node (ref "D32") (pin "A") (pinfunction "A_A") (pintype "passive"))
      (node (ref "S_D") (pin "1@1") (pinfunction "P_1@1") (pintype "passive"))
      (node (ref "S_D") (pin "1@2") (pinfunction "P_1@2") (pintype "passive"))
    )
    (net (code "61") (name "Net-(D33-PadA)") (class "Default")
      (node (ref "D33") (pin "A") (pinfunction "A_A") (pintype "passive"))
      (node (ref "S_F") (pin "1@1") (pinfunction "P_1@1") (pintype "passive"))
      (node (ref "S_F") (pin "1@2") (pinfunction "P_1@2") (pintype "passive"))
    )
    (net (code "62") (name "Net-(D34-PadA)") (class "Default")
      (node (ref "D34") (pin "A") (pinfunction "A_A") (pintype "passive"))
      (node (ref "S_G") (pin "1@1") (pinfunction "P_1@1") (pintype "passive"))
      (node (ref "S_G") (pin "1@2") (pinfunction "P_1@2") (pintype "passive"))
    )
    (net (code "63") (name "Net-(D35-PadA)") (class "Default")
      (node (ref "D35") (pin "A") (pinfunction "A_A") (pintype "passive"))
      (node (ref "S_H") (pin "1@1") (pinfunction "P_1@1") (pintype "passive"))
      (node (ref "S_H") (pin "1@2") (pinfunction "P_1@2") (pintype "passive"))
    )
    (net (code "64") (name "Net-(D36-PadA)") (class "Default")
      (node (ref "D36") (pin "A") (pinfunction "A_A") (pintype "passive"))
      (node (ref "S_J") (pin "1@1") (pinfunction "P_1@1") (pintype "passive"))
      (node (ref "S_J") (pin "1@2") (pinfunction "P_1@2") (pintype "passive"))
    )
    (net (code "65") (name "Net-(D37-PadA)") (class "Default")
      (node (ref "D37") (pin "A") (pinfunction "A_A") (pintype "passive"))
      (node (ref "S_K") (pin "1@1") (pinfunction "P_1@1") (pintype "passive"))
      (node (ref "S_K") (pin "1@2") (pinfunction "P_1@2") (pintype "passive"))
    )
    (net (code "66") (name "Net-(D38-PadA)") (class "Default")
      (node (ref "D38") (pin "A") (pinfunction "A_A") (pintype "passive"))
      (node (ref "S_L") (pin "1@1") (pinfunction "P_1@1") (pintype "passive"))
      (node (ref "S_L") (pin "1@2") (pinfunction "P_1@2") (pintype "passive"))
    )
    (net (code "67") (name "Net-(D39-PadA)") (class "Default")
      (node (ref "D39") (pin "A") (pinfunction "A_A") (pintype "passive"))
      (node (ref "S_SCLN") (pin "1@1") (pinfunction "P_1@1") (pintype "passive"))
      (node (ref "S_SCLN") (pin "1@2") (pinfunction "P_1@2") (pintype "passive"))
    )
    (net (code "68") (name "Net-(D40-PadA)") (class "Default")
      (node (ref "D40") (pin "A") (pinfunction "A_A") (pintype "passive"))
      (node (ref "S_QUOT") (pin "1@1") (pinfunction "P_1@1") (pintype "passive"))
      (node (ref "S_QUOT") (pin "1@2") (pinfunction "P_1@2") (pintype "passive"))
    )
    (net (code "69") (name "Net-(D41-PadA)") (class "Default")
      (node (ref "D41") (pin "A") (pinfunction "A_A") (pintype "passive"))
      (node (ref "S_ENT") (pin "1@1") (pinfunction "P_1@1") (pintype "passive"))
      (node (ref "S_ENT") (pin "1@2") (pinfunction "P_1@2") (pintype "passive"))
      (node (ref "S_ENT2") (pin "1@1") (pinfunction "P_1@1") (pintype "passive"))
      (node (ref "S_ENT2") (pin "1@2") (pinfunction "P_1@2") (pintype "passive"))
    )
    (net (code "70") (name "Net-(D42-PadA)") (class "Default")
      (node (ref "D42") (pin "A") (pinfunction "A_A") (pintype "passive"))
      (node (ref "S_LSFT") (pin "1@1") (pinfunction "P_1@1") (pintype "passive"))
      (node (ref "S_LSFT") (pin "1@2") (pinfunction "P_1@2") (pintype "passive"))
      (node (ref "S_LSFT2") (pin "1@1") (pinfunction "P_1@1") (pintype "passive"))
      (node (ref "S_LSFT2") (pin "1@2") (pinfunction "P_1@2") (pintype "passive"))
    )
    (net (code "71") (name "Net-(D43-PadA)") (class "Default")
      (node (ref "D43") (pin "A") (pinfunction "A_A") (pintype "passive"))
      (node (ref "S_NUBS") (pin "1@1") (pinfunction "P_1@1") (pintype "passive"))
      (node (ref "S_NUBS") (pin "1@2") (pinfunction "P_1@2") (pintype "passive"))
    )
    (net (code "72") (name "Net-(D44-PadA)") (class "Default")
      (node (ref "D44") (pin "A") (pinfunction "A_A") (pintype "passive"))
      (node (ref "S_Z") (pin "1@1") (pinfunction "P_1@1") (pintype "passive"))
      (node (ref "S_Z") (pin "1@2") (pinfunction "P_1@2") (pintype "passive"))
    )
    (net (code "73") (name "Net-(D45-PadA)") (class "Default")
      (node (ref "D45") (pin "A") (pinfunction "A_A") (pintype "passive"))
      (node (ref "S_X") (pin "1@1") (pinfunction "P_1@1") (pintype "passive"))
      (node (ref "S_X") (pin "1@2") (pinfunction "P_1@2") (pintype "passive"))
    )
    (net (code "74") (name "Net-(D46-PadA)") (class "Default")
      (node (ref "D46") (pin "A") (pinfunction "A_A") (pintype "passive"))
      (node (ref "S_C") (pin "1@1") (pinfunction "P_1@1") (pintype "passive"))
      (node (ref "S_C") (pin "1@2") (pinfunction "P_1@2") (pintype "passive"))
    )
    (net (code "75") (name "Net-(D47-PadA)") (class "Default")
      (node (ref "D47") (pin "A") (pinfunction "A_A") (pintype "passive"))
      (node (ref "S_V") (pin "1@1") (pinfunction "P_1@1") (pintype "passive"))
      (node (ref "S_V") (pin "1@2") (pinfunction "P_1@2") (pintype "passive"))
    )
    (net (code "76") (name "Net-(D48-PadA)") (class "Default")
      (node (ref "D48") (pin "A") (pinfunction "A_A") (pintype "passive"))
      (node (ref "S_B") (pin "1@1") (pinfunction "P_1@1") (pintype "passive"))
      (node (ref "S_B") (pin "1@2") (pinfunction "P_1@2") (pintype "passive"))
    )
    (net (code "77") (name "Net-(D49-PadA)") (class "Default")
      (node (ref "D49") (pin "A") (pinfunction "A_A") (pintype "passive"))
      (node (ref "S_N") (pin "1@1") (pinfunction "P_1@1") (pintype "passive"))
      (node (ref "S_N") (pin "1@2") (pinfunction "P_1@2") (pintype "passive"))
    )
    (net (code "78") (name "Net-(D50-PadA)") (class "Default")
      (node (ref "D50") (pin "A") (pinfunction "A_A") (pintype "passive"))
      (node (ref "S_M") (pin "1@1") (pinfunction "P_1@1") (pintype "passive"))
      (node (ref "S_M") (pin "1@2") (pinfunction "P_1@2") (pintype "passive"))
    )
    (net (code "79") (name "Net-(D51-PadA)") (class "Default")
      (node (ref "D51") (pin "A") (pinfunction "A_A") (pintype "passive"))
      (node (ref "S_COM") (pin "1@1") (pinfunction "P_1@1") (pintype "passive"))
      (node (ref "S_COM") (pin "1@2") (pinfunction "P_1@2") (pintype "passive"))
    )
    (net (code "80") (name "Net-(D52-PadA)") (class "Default")
      (node (ref "D52") (pin "A") (pinfunction "A_A") (pintype "passive"))
      (node (ref "S_DOT") (pin "1@1") (pinfunction "P_1@1") (pintype "passive"))
      (node (ref "S_DOT") (pin "1@2") (pinfunction "P_1@2") (pintype "passive"))
    )
    (net (code "81") (name "Net-(D53-PadA)") (class "Default")
      (node (ref "D53") (pin "A") (pinfunction "A_A") (pintype "passive"))
      (node (ref "S_SLSH") (pin "1@1") (pinfunction "P_1@1") (pintype "passive"))
      (node (ref "S_SLSH") (pin "1@2") (pinfunction "P_1@2") (pintype "passive"))
    )
    (net (code "82") (name "Net-(D55-PadA)") (class "Default")
      (node (ref "D55") (pin "A") (pinfunction "A_A") (pintype "passive"))
      (node (ref "S_LCTL") (pin "1@1") (pinfunction "P_1@1") (pintype "passive"))
      (node (ref "S_LCTL") (pin "1@2") (pinfunction "P_1@2") (pintype "passive"))
    )
    (net (code "83") (name "Net-(D56-PadA)") (class "Default")
      (node (ref "D56") (pin "A") (pinfunction "A_A") (pintype "passive"))
      (node (ref "S_LGUI") (pin "1@1") (pinfunction "P_1@1") (pintype "passive"))
      (node (ref "S_LGUI") (pin "1@2") (pinfunction "P_1@2") (pintype "passive"))
    )
    (net (code "84") (name "Net-(D57-PadA)") (class "Default")
      (node (ref "D57") (pin "A") (pinfunction "A_A") (pintype "passive"))
      (node (ref "S_LALT") (pin "1@1") (pinfunction "P_1@1") (pintype "passive"))
      (node (ref "S_LALT") (pin "1@2") (pinfunction "P_1@2") (pintype "passive"))
    )
    (net (code "85") (name "Net-(D58-PadA)") (class "Default")
      (node (ref "D58") (pin "A") (pinfunction "A_A") (pintype "passive"))
      (node (ref "S_SPC") (pin "1@1") (pinfunction "P_1@1") (pintype "passive"))
      (node (ref "S_SPC") (pin "1@2") (pinfunction "P_1@2") (pintype "passive"))
    )
    (net (code "86") (name "Net-(D59-PadA)") (class "Default")
      (node (ref "D59") (pin "A") (pinfunction "A_A") (pintype "passive"))
      (node (ref "S_FN1") (pin "1@1") (pinfunction "P_1@1") (pintype "passive"))
      (node (ref "S_FN1") (pin "1@2") (pinfunction "P_1@2") (pintype "passive"))
    )
    (net (code "87") (name "Net-(D60-PadA)") (class "Default")
      (node (ref "D60") (pin "A") (pinfunction "A_A") (pintype "passive"))
      (node (ref "S_APP") (pin "1@1") (pinfunction "P_1@1") (pintype "passive"))
      (node (ref "S_APP") (pin "1@2") (pinfunction "P_1@2") (pintype "passive"))
    )
    (net (code "88") (name "Net-(D61-PadA)") (class "Default")
      (node (ref "D61") (pin "A") (pinfunction "A_A") (pintype "passive"))
      (node (ref "S_RALT") (pin "1@1") (pinfunction "P_1@1") (pintype "passive"))
      (node (ref "S_RALT") (pin "1@2") (pinfunction "P_1@2") (pintype "passive"))
    )
    (net (code "89") (name "Net-(D62-PadA)") (class "Default")
      (node (ref "D62") (pin "A") (pinfunction "A_A") (pintype "passive"))
      (node (ref "S_RCTL") (pin "1@1") (pinfunction "P_1@1") (pintype "passive"))
      (node (ref "S_RCTL") (pin "1@2") (pinfunction "P_1@2") (pintype "passive"))
    )
    (net (code "90") (name "Net-(D65-PadA)") (class "Default")
      (node (ref "D65") (pin "A") (pinfunction "A_A") (pintype "passive"))
      (node (ref "DIP-SW") (pin "1") (pinfunction "1_1") (pintype "passive"))
    )
    (net (code "91") (name "Net-(D66-PadA)") (class "Default")
      (node (ref "D66") (pin "A") (pinfunction "A_A") (pintype "passive"))
      (node (ref "DIP-SW") (pin "2") (pinfunction "2_2") (pintype "passive"))
    )
    (net (code "92") (name "Net-(D67-PadA)") (class "Default")
      (node (ref "D67") (pin "A") (pinfunction "A_A") (pintype "passive"))
      (node (ref "DIP-SW") (pin "3") (pinfunction "3_3") (pintype "passive"))
    )
    (net (code "93") (name "Net-(DIP-SW-Pad4)") (class "Default")
      (node (ref "DIP-SW") (pin "4") (pinfunction "4_4") (pintype "passive"))
      (node (ref "J-VIN") (pin "2") (pinfunction "2_2") (pintype "passive"))
      (node (ref "R3") (pin "2") (pinfunction "2_2") (pintype "passive"))
    )
    (net (code "94") (name "Net-(J-UBS-CC1)") (class "Default")
      (node (ref "J-UBS") (pin "A5") (pinfunction "CC1_A5") (pintype "bidirectional"))
      (node (ref "R1") (pin "1") (pinfunction "1_1") (pintype "passive"))
    )
    (net (code "95") (name "Net-(J-UBS-CC2)") (class "Default")
      (node (ref "J-UBS") (pin "B5") (pinfunction "CC2_B5") (pintype "bidirectional"))
      (node (ref "R2") (pin "1") (pinfunction "1_1") (pintype "passive"))
    )
    (net (code "96") (name "Net-(LED-5-2_DOUT)") (class "Default")
      (node (ref "LED-5") (pin "2-DOUT") (pinfunction "2_DOUT_2-DOUT") (pintype "output"))
      (node (ref "LED-6") (pin "4-DIN") (pinfunction "4_DIN_4-DIN") (pintype "input"))
    )
    (net (code "97") (name "Net-(LED-5-4_DIN)") (class "Default")
      (node (ref "LED-5") (pin "4-DIN") (pinfunction "4_DIN_4-DIN") (pintype "input"))
      (node (ref "LED-CL") (pin "2-DOUT") (pinfunction "2_DOUT_2-DOUT") (pintype "output"))
    )
    (net (code "98") (name "Net-(LED-6-2_DOUT)") (class "Default")
      (node (ref "LED-6") (pin "2-DOUT") (pinfunction "2_DOUT_2-DOUT") (pintype "output"))
      (node (ref "LED-7") (pin "4-DIN") (pinfunction "4_DIN_4-DIN") (pintype "input"))
    )
    (net (code "99") (name "Net-(LED-7-2_DOUT)") (class "Default")
      (node (ref "LED-7") (pin "2-DOUT") (pinfunction "2_DOUT_2-DOUT") (pintype "output"))
      (node (ref "LED-8") (pin "4-DIN") (pinfunction "4_DIN_4-DIN") (pintype "input"))
    )
    (net (code "100") (name "Net-(LED-8-2_DOUT)") (class "Default")
      (node (ref "J-LED") (pin "2") (pinfunction "2_2") (pintype "passive"))
      (node (ref "LED-8") (pin "2-DOUT") (pinfunction "2_DOUT_2-DOUT") (pintype "output"))
    )
    (net (code "101") (name "Net-(LED-CL-4_DIN)") (class "Default")
      (node (ref "LED-CL") (pin "4-DIN") (pinfunction "4_DIN_4-DIN") (pintype "input"))
      (node (ref "R7") (pin "1") (pinfunction "1_1") (pintype "passive"))
    )
    (net (code "102") (name "Net-(S_BSPC2-P)") (class "Default")
      (node (ref "D14") (pin "A") (pinfunction "A_A") (pintype "passive"))
      (node (ref "S_BSPC") (pin "1@1") (pinfunction "P_1@1") (pintype "passive"))
      (node (ref "S_BSPC") (pin "1@2") (pinfunction "P_1@2") (pintype "passive"))
      (node (ref "S_BSPC2") (pin "1") (pinfunction "P_1") (pintype "passive"))
    )
    (net (code "103") (name "Net-(S_CAPS2-S)") (class "Default")
      (node (ref "D29") (pin "A") (pinfunction "A_A") (pintype "passive"))
      (node (ref "S_CAPS") (pin "1@1") (pinfunction "P_1@1") (pintype "passive"))
      (node (ref "S_CAPS") (pin "1@2") (pinfunction "P_1@2") (pintype "passive"))
      (node (ref "S_CAPS2") (pin "2") (pinfunction "S_2") (pintype "passive"))
    )
    (net (code "104") (name "Net-(S_FN-P)") (class "Default")
      (node (ref "D63") (pin "A") (pinfunction "A_A") (pintype "passive"))
      (node (ref "S_FN") (pin "1") (pinfunction "P_1") (pintype "passive"))
    )
    (net (code "105") (name "Net-(S_RSFT2-P)") (class "Default")
      (node (ref "D54") (pin "A") (pinfunction "A_A") (pintype "passive"))
      (node (ref "S_RSFT") (pin "1@1") (pinfunction "P_1@1") (pintype "passive"))
      (node (ref "S_RSFT") (pin "1@2") (pinfunction "P_1@2") (pintype "passive"))
      (node (ref "S_RSFT2") (pin "1") (pinfunction "P_1") (pintype "passive"))
    )
    (net (code "106") (name "Net-(S_SPARE-P)") (class "Default")
      (node (ref "D64") (pin "A") (pinfunction "A_A") (pintype "passive"))
      (node (ref "S_SPARE") (pin "1") (pinfunction "P_1") (pintype "passive"))
    )
    (net (code "107") (name "Net-(X1-USBHOST_D+)") (class "Default")
      (node (ref "J-HOST") (pin "1") (pinfunction "1_1") (pintype "passive"))
      (node (ref "X1") (pin "35") (pinfunction "USBHOST_D+_35") (pintype "bidirectional"))
    )
    (net (code "108") (name "Net-(X1-USBHOST_D-)") (class "Default")
      (node (ref "J-HOST") (pin "2") (pinfunction "2_2") (pintype "passive"))
      (node (ref "X1") (pin "37") (pinfunction "USBHOST_D-_37") (pintype "bidirectional"))
    )
    (net (code "109") (name "SC1") (class "Default")
      (node (ref "JP-GND") (pin "1") (pinfunction "1_1") (pintype "passive"))
    )
    (net (code "110") (name "SCK") (class "Default")
      (node (ref "M1") (pin "6") (pinfunction "CLK_6") (pintype "bidirectional"))
      (node (ref "R8") (pin "2") (pinfunction "2_2") (pintype "passive"))
      (node (ref "X1") (pin "57") (pinfunction "SPI_SCK_57") (pintype "bidirectional"))
    )
    (net (code "111") (name "VBUS") (class "Default")
      (node (ref "ESD") (pin "P$5") (pinfunction "P$5_P$5") (pintype "bidirectional"))
      (node (ref "J-UBS") (pin "VBUS1") (pinfunction "VBUS_VBUS1") (pintype "bidirectional"))
      (node (ref "J-UBS") (pin "VBUS2") (pinfunction "VBUS_VBUS2") (pintype "bidirectional"))
      (node (ref "PTC") (pin "P$1") (pinfunction "1_P$1") (pintype "passive"))
    )
    (net (code "112") (name "VCC") (class "Default")
      (node (ref "C01") (pin "1") (pinfunction "1_1") (pintype "passive"))
      (node (ref "C02") (pin "1") (pinfunction "1_1") (pintype "passive"))
      (node (ref "C03") (pin "1") (pinfunction "1_1") (pintype "passive"))
      (node (ref "C13") (pin "1") (pinfunction "1_1") (pintype "passive"))
      (node (ref "D00") (pin "A") (pinfunction "A_A") (pintype "passive"))
      (node (ref "J-52") (pin "3") (pinfunction "3_3") (pintype "passive"))
      (node (ref "LM1117") (pin "2") (pinfunction "OUT_2") (pintype "output"))
      (node (ref "M1") (pin "3") (pinfunction "~{WP}_3") (pintype "bidirectional"))
      (node (ref "M1") (pin "7") (pinfunction "~{HLD}_7") (pintype "bidirectional"))
      (node (ref "M1") (pin "8") (pinfunction "VCC_8") (pintype "bidirectional"))
      (node (ref "R9") (pin "2") (pinfunction "2_2") (pintype "passive"))
      (node (ref "X1") (pin "2") (pinfunction "3.3V_2") (pintype "bidirectional"))
      (node (ref "X1") (pin "4") (pinfunction "3.3V_EN_4") (pintype "bidirectional"))
      (node (ref "X1") (pin "74") (pinfunction "3.3V_74") (pintype "bidirectional"))
    )
    (net (code "113") (name "VIN{slash}3") (class "Default")
      (node (ref "R3") (pin "1") (pinfunction "1_1") (pintype "passive"))
      (node (ref "R4") (pin "2") (pinfunction "2_2") (pintype "passive"))
      (node (ref "X1") (pin "49") (pinfunction "BATT_VIN/3_49") (pintype "bidirectional"))
    )
    (net (code "114") (name "VSUP") (class "Default")
      (node (ref "74AH") (pin "6") (pinfunction "5_VCC_6") (pintype "power_in"))
      (node (ref "C04") (pin "1") (pinfunction "1_1") (pintype "passive"))
      (node (ref "C05") (pin "1") (pinfunction "1_1") (pintype "passive"))
      (node (ref "C07") (pin "1") (pinfunction "1_1") (pintype "passive"))
      (node (ref "C08") (pin "1") (pinfunction "1_1") (pintype "passive"))
      (node (ref "C09") (pin "1") (pinfunction "1_1") (pintype "passive"))
      (node (ref "C10") (pin "1") (pinfunction "1_1") (pintype "passive"))
      (node (ref "C11") (pin "1") (pinfunction "1_1") (pintype "passive"))
      (node (ref "C12") (pin "1") (pinfunction "1_1") (pintype "passive"))
      (node (ref "D00") (pin "C") (pinfunction "C_C") (pintype "passive"))
      (node (ref "DIP-SW") (pin "5") (pinfunction "5_5") (pintype "passive"))
      (node (ref "J-LED") (pin "3") (pinfunction "3_3") (pintype "passive"))
      (node (ref "J-UDB") (pin "1") (pinfunction "VCC_1") (pintype "power_in"))
      (node (ref "J-VIN") (pin "1") (pinfunction "1_1") (pintype "passive"))
      (node (ref "LED-5") (pin "1-VDD") (pinfunction "1_VDD_1-VDD") (pintype "power_in"))
      (node (ref "LED-6") (pin "1-VDD") (pinfunction "1_VDD_1-VDD") (pintype "power_in"))
      (node (ref "LED-7") (pin "1-VDD") (pinfunction "1_VDD_1-VDD") (pintype "power_in"))
      (node (ref "LED-8") (pin "1-VDD") (pinfunction "1_VDD_1-VDD") (pintype "power_in"))
      (node (ref "LED-CL") (pin "1-VDD") (pinfunction "1_VDD_1-VDD") (pintype "power_in"))
      (node (ref "LM1117") (pin "3") (pinfunction "IN_3") (pintype "input"))
      (node (ref "PTC") (pin "P$2") (pinfunction "2_P$2") (pintype "passive"))
      (node (ref "TVS") (pin "P$1") (pinfunction "1_P$1") (pintype "passive"))
      (node (ref "X1") (pin "9") (pinfunction "USB_VIN_9") (pintype "bidirectional"))
    )
    (net (code "115") (name "unconnected-(LM1117-OUT-Pad4)") (class "Default")
      (node (ref "LM1117") (pin "4") (pinfunction "OUT_4") (pintype "output"))
    )
    (net (code "116") (name "unconnected-(X1-AUD_MCLK-Pad58)") (class "Default")
      (node (ref "X1") (pin "58") (pinfunction "AUD_MCLK_58") (pintype "bidirectional"))
    )
    (net (code "117") (name "unconnected-(X1-CAN-RX-Pad41)") (class "Default")
      (node (ref "X1") (pin "41") (pinfunction "CAN-RX_41") (pintype "bidirectional"))
    )
    (net (code "118") (name "unconnected-(X1-CAN-TX-Pad43)") (class "Default")
      (node (ref "X1") (pin "43") (pinfunction "CAN-TX_43") (pintype "bidirectional"))
    )
    (net (code "119") (name "unconnected-(X1-CTS1-Pad15)") (class "Default")
      (node (ref "X1") (pin "15") (pinfunction "CTS1_15") (pintype "bidirectional"))
    )
    (net (code "120") (name "unconnected-(X1-G4{slash}BUS4-Pad48)") (class "Default")
      (node (ref "X1") (pin "48") (pinfunction "G4/BUS4_48") (pintype "bidirectional"))
    )
    (net (code "121") (name "unconnected-(X1-G5{slash}BUS5-Pad73)") (class "Default")
      (node (ref "X1") (pin "73") (pinfunction "G5/BUS5_73") (pintype "bidirectional"))
    )
    (net (code "122") (name "unconnected-(X1-G6{slash}BUS6-Pad71)") (class "Default")
      (node (ref "X1") (pin "71") (pinfunction "G6/BUS6_71") (pintype "bidirectional"))
    )
    (net (code "123") (name "unconnected-(X1-G7{slash}BUS7-Pad69)") (class "Default")
      (node (ref "X1") (pin "69") (pinfunction "G7/BUS7_69") (pintype "bidirectional"))
    )
    (net (code "124") (name "unconnected-(X1-G8-Pad67)") (class "Default")
      (node (ref "X1") (pin "67") (pinfunction "G8_67") (pintype "bidirectional"))
    )
    (net (code "125") (name "unconnected-(X1-G9{slash}ADC_D-{slash}CAM_HSYNC-Pad65)") (class "Default")
      (node (ref "X1") (pin "65") (pinfunction "G9/ADC_D-/CAM_HSYNC_65") (pintype "bidirectional"))
    )
    (net (code "126") (name "unconnected-(X1-G11-Pad8)") (class "Default")
      (node (ref "X1") (pin "8") (pinfunction "G11_8") (pintype "bidirectional"))
    )
    (net (code "127") (name "unconnected-(X1-I2C_SCL1-Pad53)") (class "Default")
      (node (ref "X1") (pin "53") (pinfunction "I2C_SCL1_53") (pintype "bidirectional"))
    )
    (net (code "128") (name "unconnected-(X1-I2C_SDA1-Pad51)") (class "Default")
      (node (ref "X1") (pin "51") (pinfunction "I2C_SDA1_51") (pintype "bidirectional"))
    )
    (net (code "129") (name "unconnected-(X1-RTC_3V-Pad72)") (class "Default")
      (node (ref "X1") (pin "72") (pinfunction "RTC_3V_72") (pintype "bidirectional"))
    )
    (net (code "130") (name "unconnected-(X1-RTS1-Pad13)") (class "Default")
      (node (ref "X1") (pin "13") (pinfunction "RTS1_13") (pintype "bidirectional"))
    )
    (net (code "131") (name "unconnected-(X1-RX2-Pad20)") (class "Default")
      (node (ref "X1") (pin "20") (pinfunction "RX2_20") (pintype "bidirectional"))
    )
    (net (code "132") (name "unconnected-(X1-SDIO_DATA1-Pad66)") (class "Default")
      (node (ref "X1") (pin "66") (pinfunction "SDIO_DATA1_66") (pintype "bidirectional"))
    )
    (net (code "133") (name "unconnected-(X1-SDIO_DATA2-Pad68)") (class "Default")
      (node (ref "X1") (pin "68") (pinfunction "SDIO_DATA2_68") (pintype "bidirectional"))
    )
    (net (code "134") (name "unconnected-(X1-SPI_SCK1{slash}SDIO_CLK-Pad60)") (class "Default")
      (node (ref "X1") (pin "60") (pinfunction "SPI_SCK1/SDIO_CLK_60") (pintype "bidirectional"))
    )
    (net (code "135") (name "unconnected-(X1-SPI_SDI1{slash}SDIO_DATA0-Pad64)") (class "Default")
      (node (ref "X1") (pin "64") (pinfunction "SPI_SDI1/SDIO_DATA0_64") (pintype "bidirectional"))
    )
    (net (code "136") (name "unconnected-(X1-SPI_SDO1{slash}SDIO_CMD-Pad62)") (class "Default")
      (node (ref "X1") (pin "62") (pinfunction "SPI_SDO1/SDIO_CMD_62") (pintype "bidirectional"))
    )
    (net (code "137") (name "unconnected-(X1-SPI_~{CS1}{slash}SDIO_DATA3-Pad70)") (class "Default")
      (node (ref "X1") (pin "70") (pinfunction "SPI_~{CS1}/SDIO_DATA3_70") (pintype "bidirectional"))
    )
    (net (code "138") (name "unconnected-(X1-SWDCK-Pad21)") (class "Default")
      (node (ref "X1") (pin "21") (pinfunction "SWDCK_21") (pintype "bidirectional"))
    )
    (net (code "139") (name "unconnected-(X1-SWDIO-Pad23)") (class "Default")
      (node (ref "X1") (pin "23") (pinfunction "SWDIO_23") (pintype "bidirectional"))
    )
    (net (code "140") (name "unconnected-(X1-TX2-Pad22)") (class "Default")
      (node (ref "X1") (pin "22") (pinfunction "TX2_22") (pintype "bidirectional"))
    )
    (net (code "141") (name "~{BOOT}") (class "Default")
      (node (ref "C14") (pin "1") (pinfunction "1_1") (pintype "passive"))
      (node (ref "D80") (pin "1") (pinfunction "A1_1") (pintype "passive"))
      (node (ref "S2") (pin "2") (pinfunction "3_2") (pintype "passive"))
      (node (ref "X1") (pin "11") (pinfunction "~{BOOT}_11") (pintype "bidirectional"))
    )
    (net (code "142") (name "~{RESET}") (class "Default")
      (node (ref "D80") (pin "2") (pinfunction "A2_2") (pintype "passive"))
      (node (ref "S1") (pin "2") (pinfunction "3_2") (pintype "passive"))
      (node (ref "X1") (pin "6") (pinfunction "~{RESET}_6") (pintype "bidirectional"))
    )
  )
)
